# Preselector_-_Copy.net
KiCad netlist of a schematic drawn in EAGLE
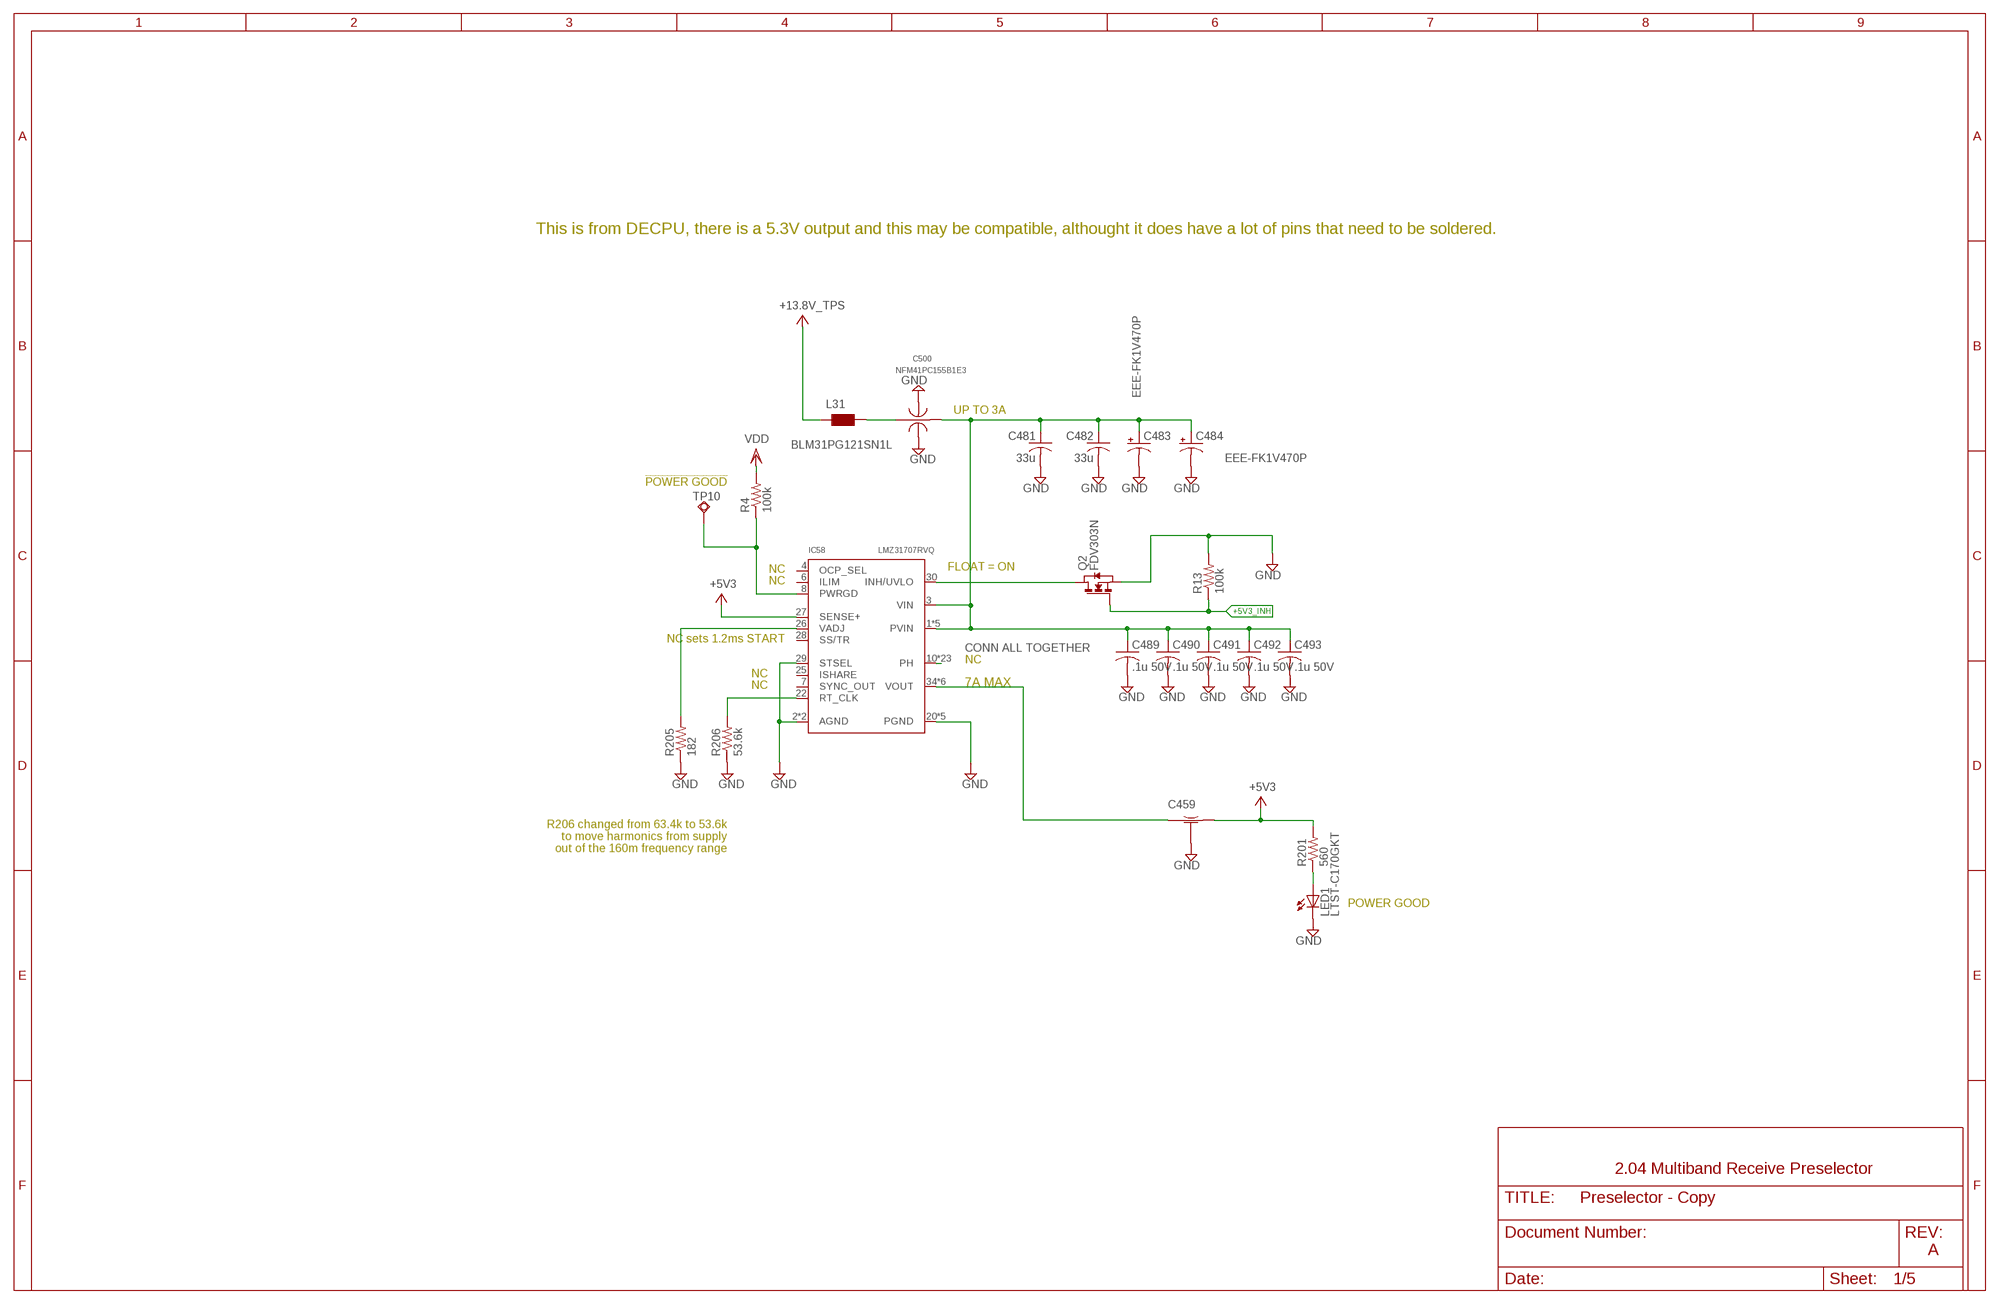
[diagram p0: schematic, sheet 1]
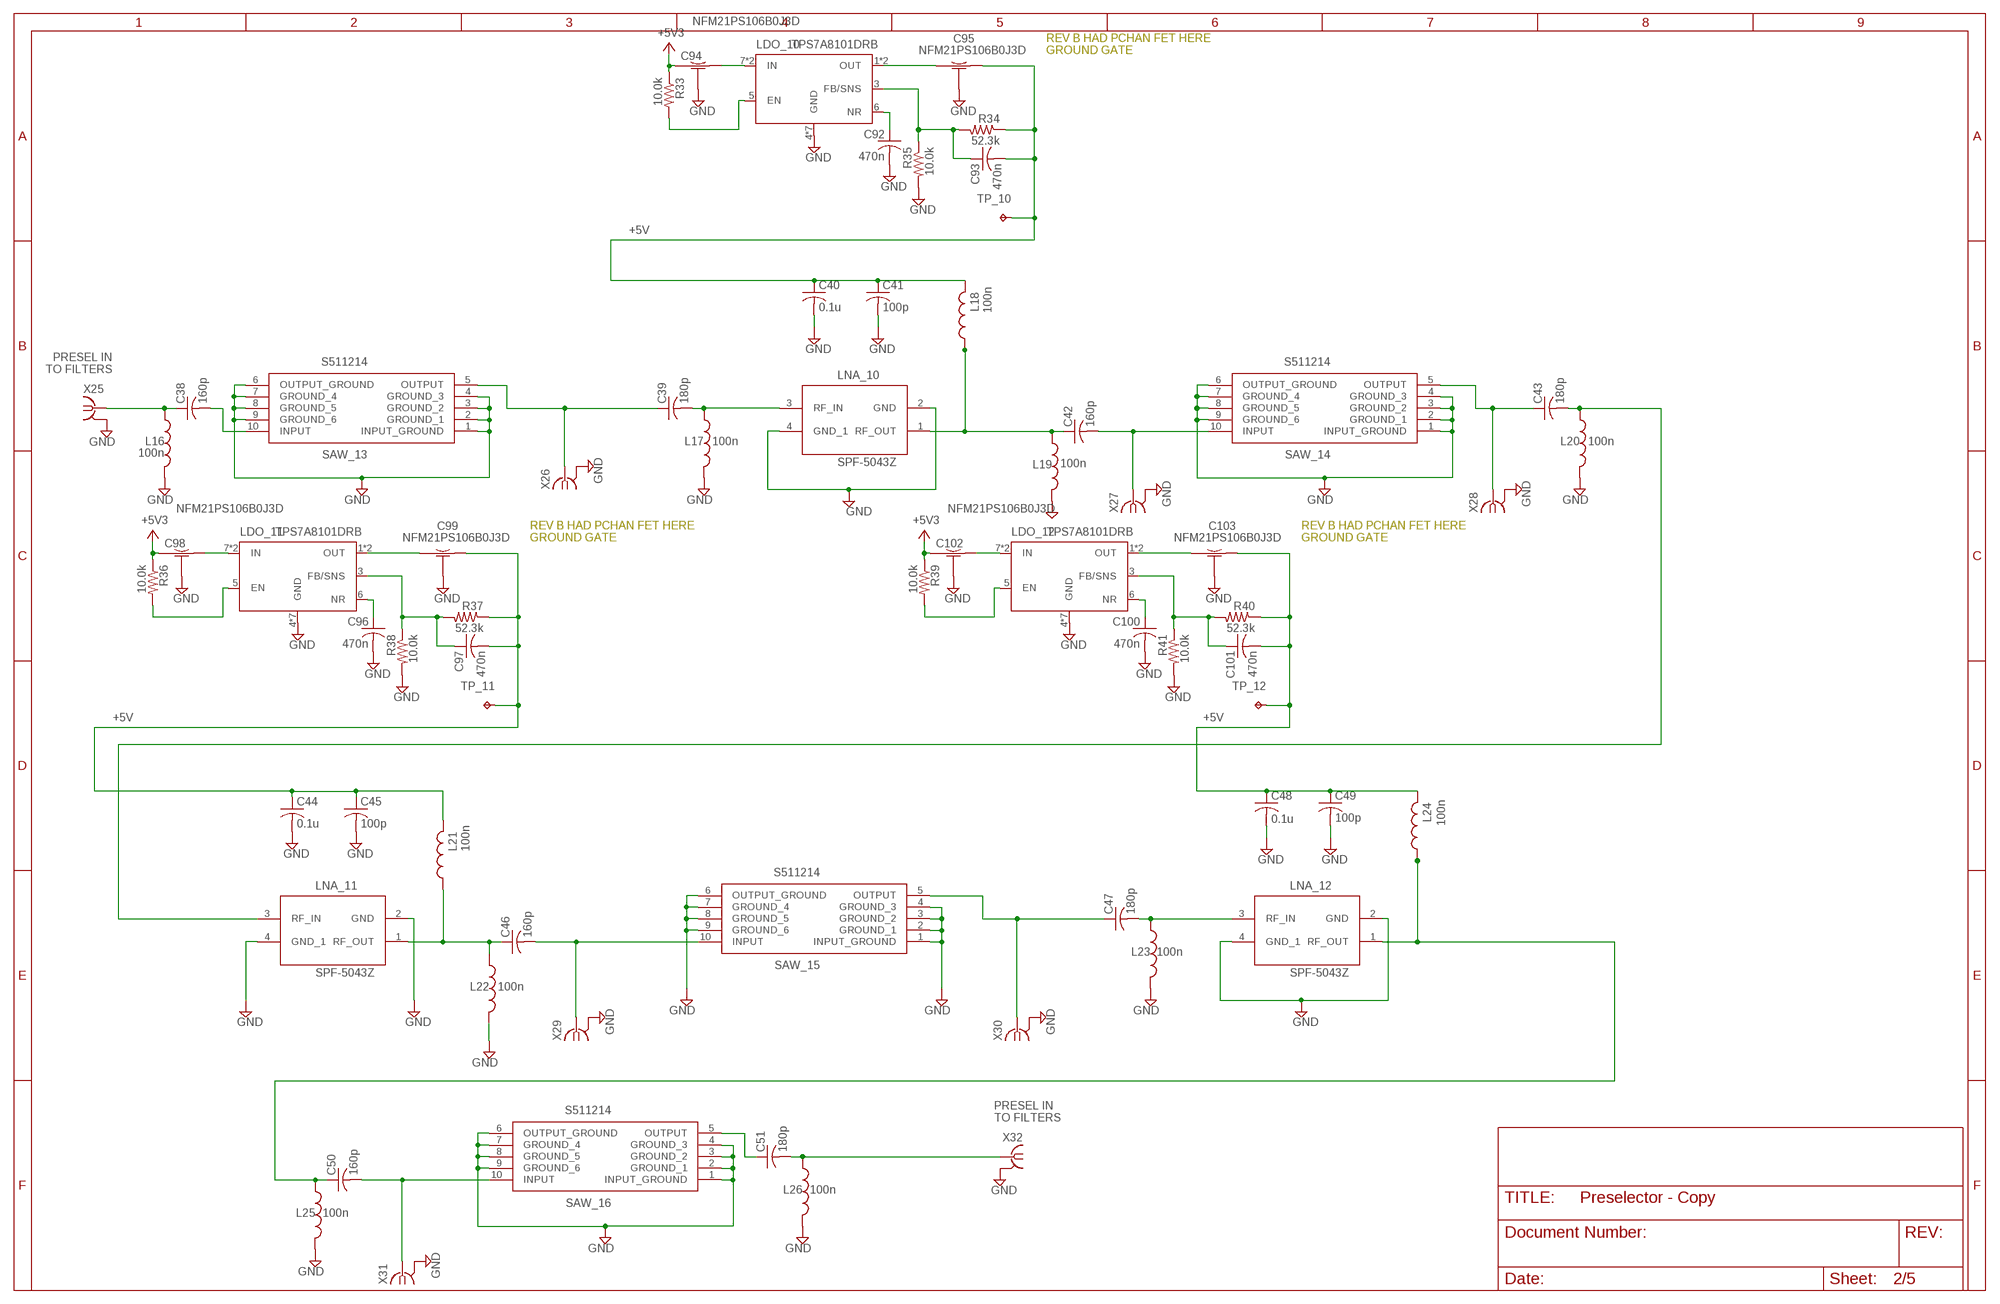
[diagram p1: schematic, sheet 2]
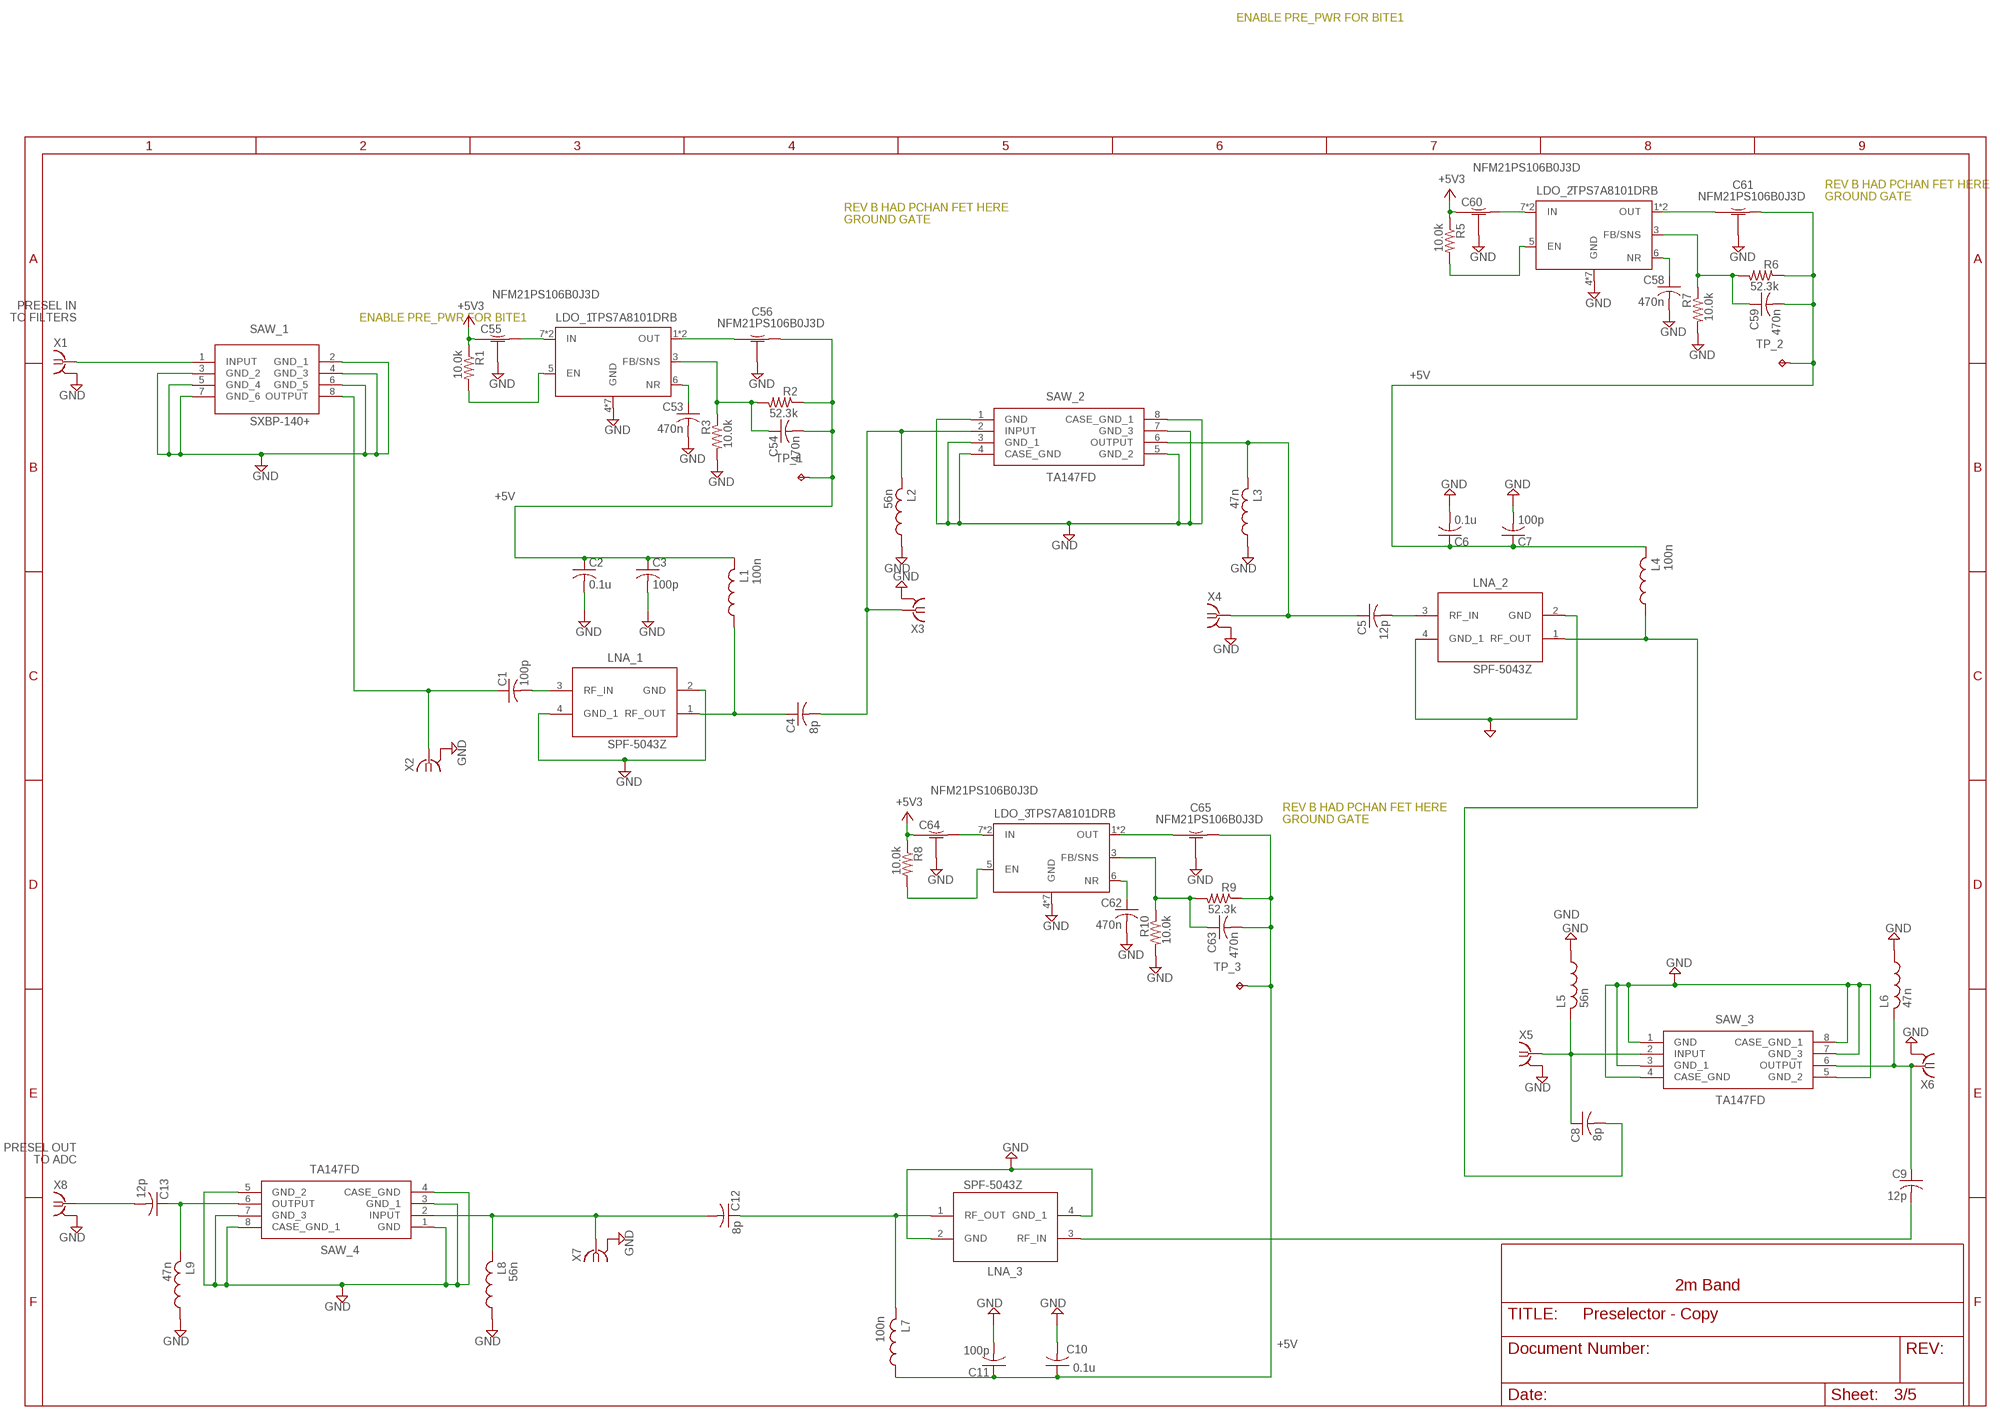
[diagram p2: schematic, sheet 3]
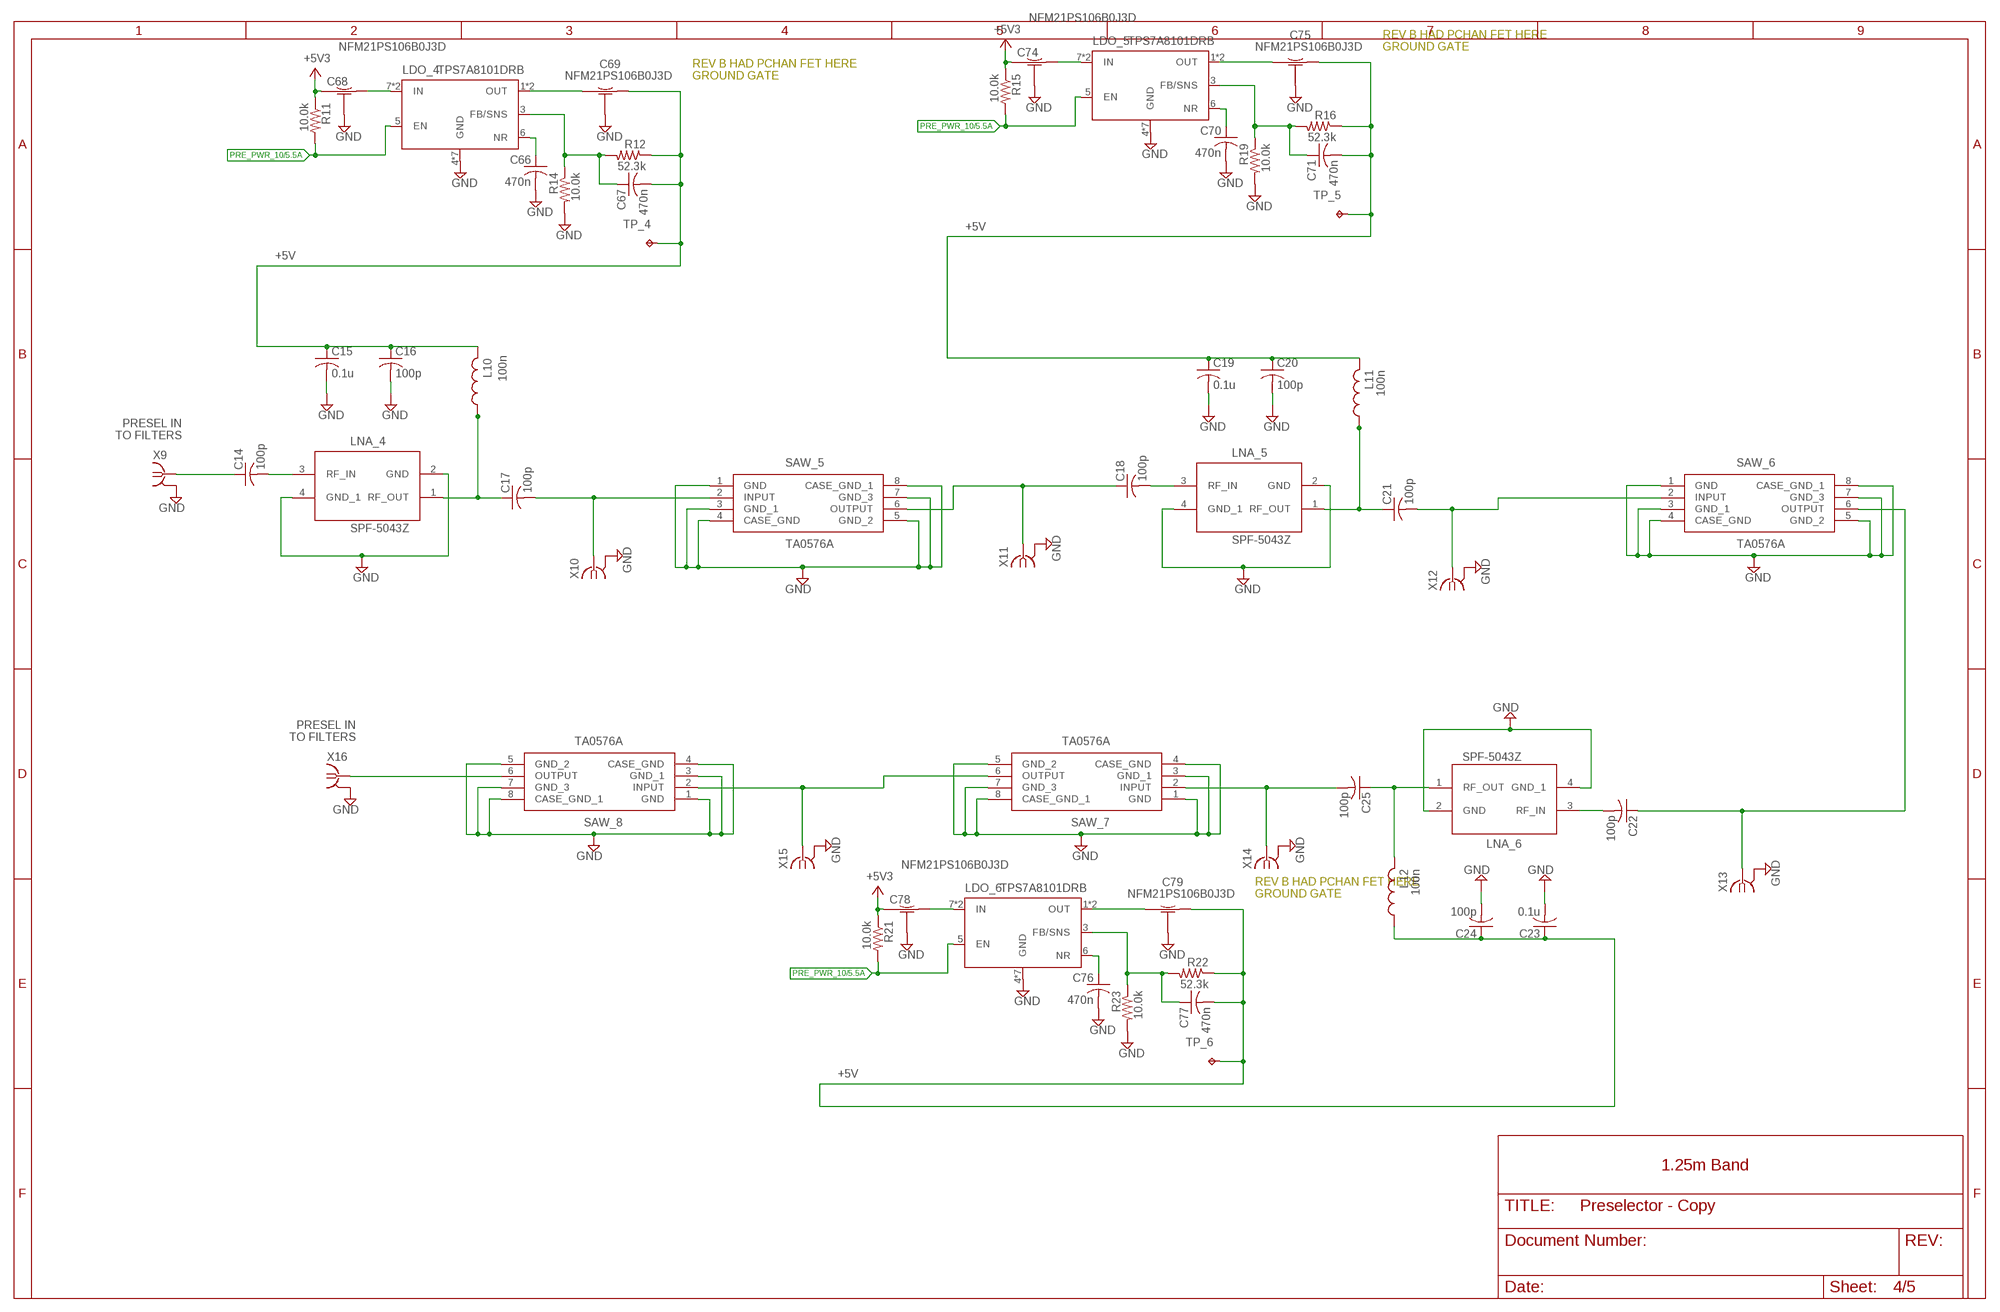
[diagram p3: schematic, sheet 4]
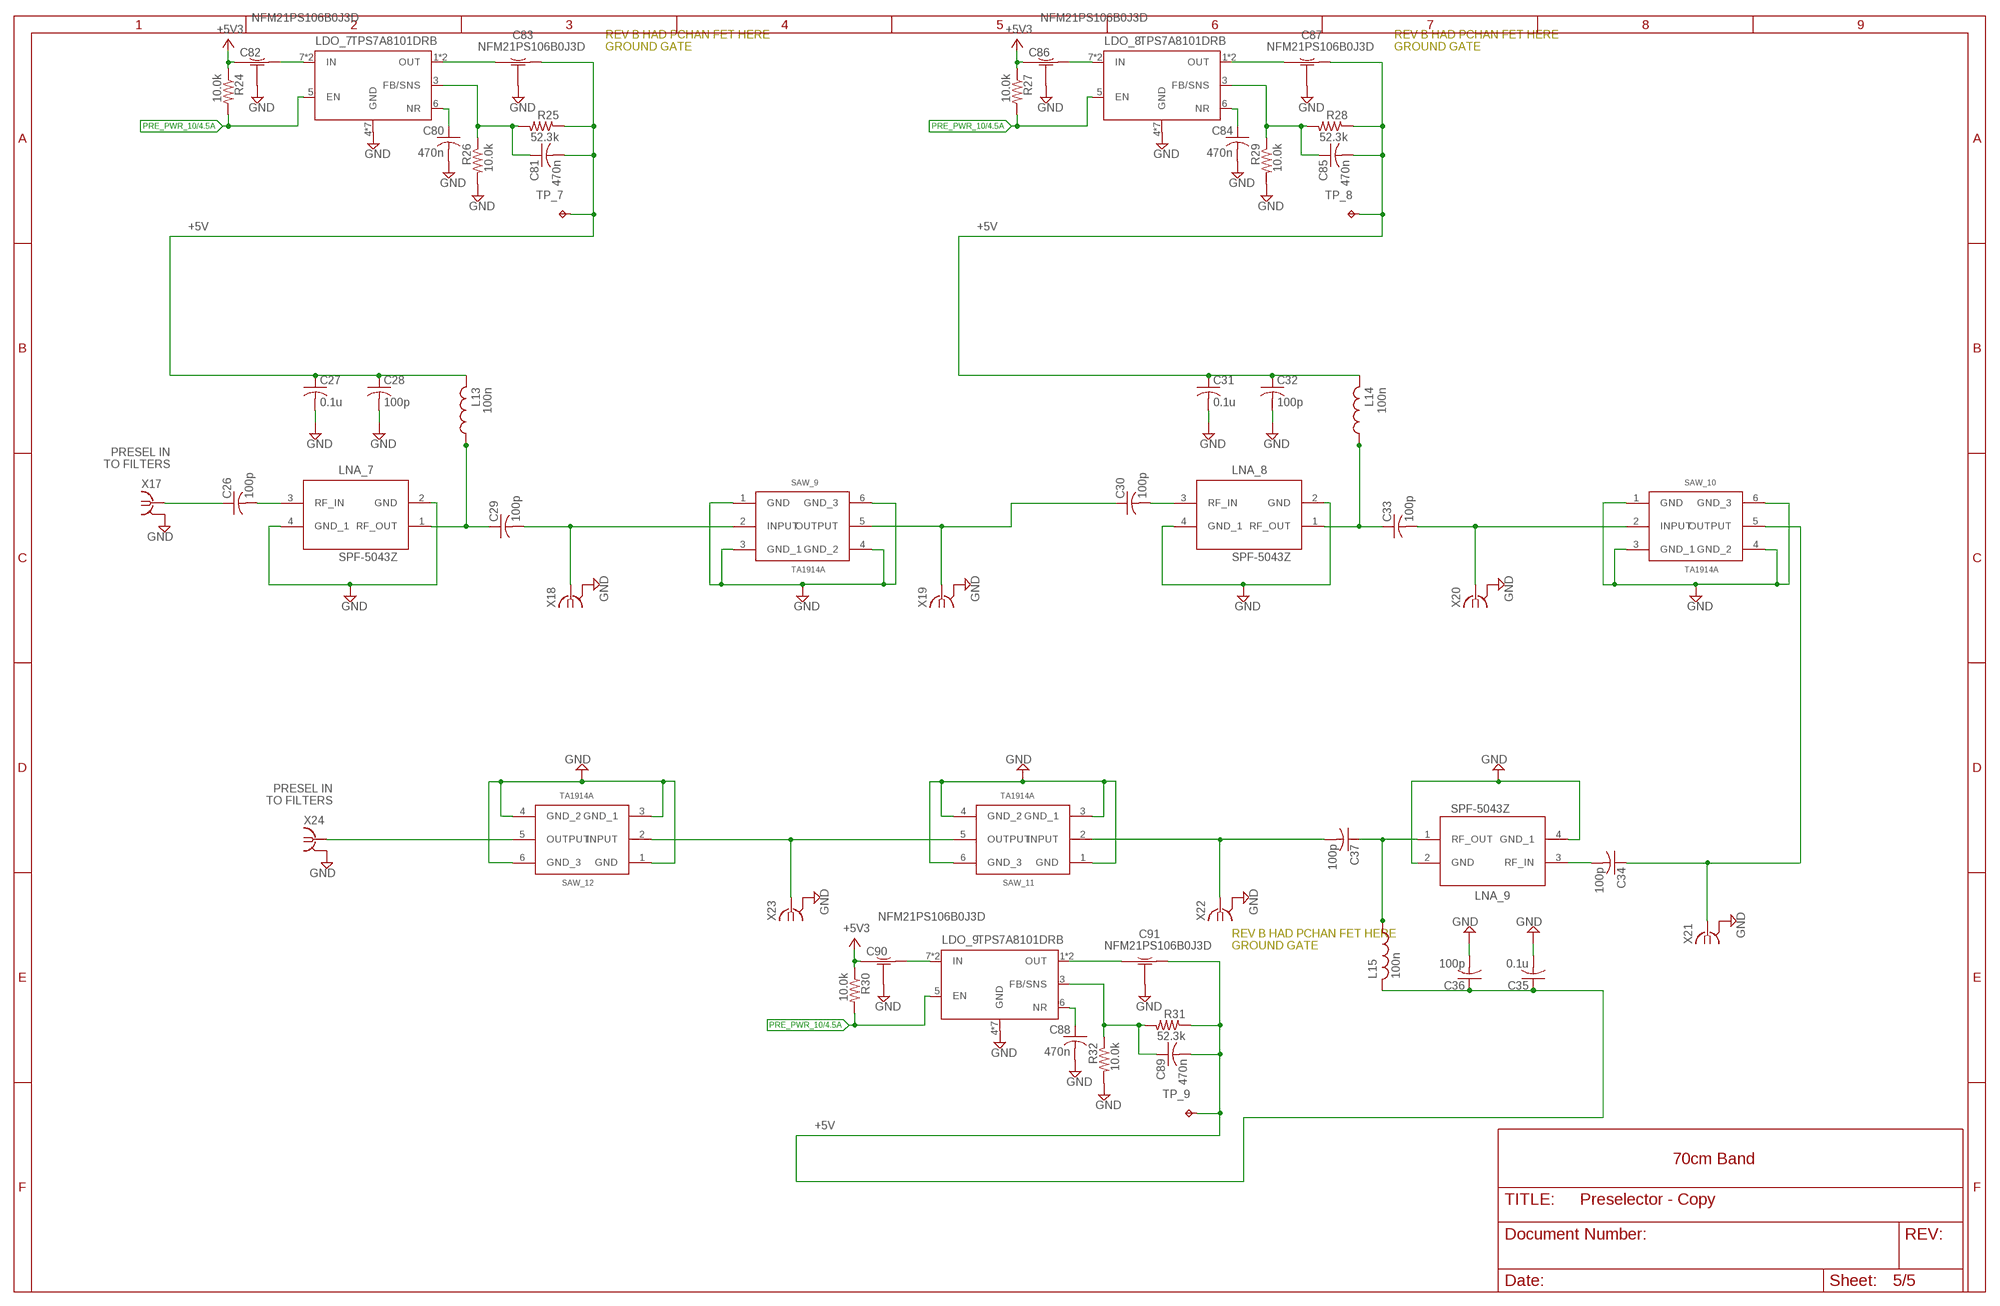
[diagram p4: schematic, sheet 5]

(export (version "E")
  (design (tool "Eeschema 10.0.6"))
  (components
    (comp (ref "C1")
      (value "100p")
      (footprint "eagle-import:C0603K")
      (libsource (lib "eagle-import") (part "C-USC0603K"))
    )
    (comp (ref "C2")
      (value "0.1u")
      (footprint "eagle-import:C0603K")
      (libsource (lib "eagle-import") (part "C-USC0603K"))
    )
    (comp (ref "C3")
      (value "100p")
      (footprint "eagle-import:C0603K")
      (libsource (lib "eagle-import") (part "C-USC0603K"))
    )
    (comp (ref "C4")
      (value "8p")
      (footprint "eagle-import:C0603K")
      (libsource (lib "eagle-import") (part "C-USC0603K"))
    )
    (comp (ref "C5")
      (value "12p")
      (footprint "eagle-import:C0603K")
      (libsource (lib "eagle-import") (part "C-USC0603K"))
    )
    (comp (ref "C6")
      (value "0.1u")
      (footprint "eagle-import:C0603K")
      (libsource (lib "eagle-import") (part "C-USC0603K"))
    )
    (comp (ref "C7")
      (value "100p")
      (footprint "eagle-import:C0603K")
      (libsource (lib "eagle-import") (part "C-USC0603K"))
    )
    (comp (ref "C8")
      (value "8p")
      (footprint "eagle-import:C0603K")
      (libsource (lib "eagle-import") (part "C-USC0603K"))
    )
    (comp (ref "C9")
      (value "12p")
      (footprint "eagle-import:C0603K")
      (libsource (lib "eagle-import") (part "C-USC0603K"))
    )
    (comp (ref "C10")
      (value "0.1u")
      (footprint "eagle-import:C0603K")
      (libsource (lib "eagle-import") (part "C-USC0603K"))
    )
    (comp (ref "C11")
      (value "100p")
      (footprint "eagle-import:C0603K")
      (libsource (lib "eagle-import") (part "C-USC0603K"))
    )
    (comp (ref "C12")
      (value "8p")
      (footprint "eagle-import:C0603K")
      (libsource (lib "eagle-import") (part "C-USC0603K"))
    )
    (comp (ref "C13")
      (value "12p")
      (footprint "eagle-import:C0603K")
      (libsource (lib "eagle-import") (part "C-USC0603K"))
    )
    (comp (ref "C53")
      (value "470n")
      (footprint "eagle-import:C0402K")
      (libsource (lib "eagle-import") (part "C-USC0402K"))
    )
    (comp (ref "C54")
      (value "470n")
      (footprint "eagle-import:C0402K")
      (libsource (lib "eagle-import") (part "C-USC0402K"))
    )
    (comp (ref "C55")
      (value "NFM21PS106B0J3D")
      (footprint "eagle-import:NFM21PS")
      (libsource (lib "eagle-import") (part "NFM21PS"))
    )
    (comp (ref "C56")
      (value "NFM21PS106B0J3D")
      (footprint "eagle-import:NFM21PS")
      (libsource (lib "eagle-import") (part "NFM21PS"))
    )
    (comp (ref "C58")
      (value "470n")
      (footprint "eagle-import:C0402K")
      (libsource (lib "eagle-import") (part "C-USC0402K"))
    )
    (comp (ref "C59")
      (value "470n")
      (footprint "eagle-import:C0402K")
      (libsource (lib "eagle-import") (part "C-USC0402K"))
    )
    (comp (ref "C60")
      (value "NFM21PS106B0J3D")
      (footprint "eagle-import:NFM21PS")
      (libsource (lib "eagle-import") (part "NFM21PS"))
    )
    (comp (ref "C61")
      (value "NFM21PS106B0J3D")
      (footprint "eagle-import:NFM21PS")
      (libsource (lib "eagle-import") (part "NFM21PS"))
    )
    (comp (ref "C62")
      (value "470n")
      (footprint "eagle-import:C0402K")
      (libsource (lib "eagle-import") (part "C-USC0402K"))
    )
    (comp (ref "C63")
      (value "470n")
      (footprint "eagle-import:C0402K")
      (libsource (lib "eagle-import") (part "C-USC0402K"))
    )
    (comp (ref "C64")
      (value "NFM21PS106B0J3D")
      (footprint "eagle-import:NFM21PS")
      (libsource (lib "eagle-import") (part "NFM21PS"))
    )
    (comp (ref "C65")
      (value "NFM21PS106B0J3D")
      (footprint "eagle-import:NFM21PS")
      (libsource (lib "eagle-import") (part "NFM21PS"))
    )
    (comp (ref "L1")
      (value "100n")
      (footprint "eagle-import:C1206")
      (libsource (lib "eagle-import") (part "L-US1206"))
    )
    (comp (ref "L2")
      (value "56n")
      (footprint "eagle-import:C1206")
      (libsource (lib "eagle-import") (part "L-US1206"))
    )
    (comp (ref "L3")
      (value "47n")
      (footprint "eagle-import:C1206")
      (libsource (lib "eagle-import") (part "L-US1206"))
    )
    (comp (ref "L4")
      (value "100n")
      (footprint "eagle-import:C1206")
      (libsource (lib "eagle-import") (part "L-US1206"))
    )
    (comp (ref "L5")
      (value "56n")
      (footprint "eagle-import:C1206")
      (libsource (lib "eagle-import") (part "L-US1206"))
    )
    (comp (ref "L6")
      (value "47n")
      (footprint "eagle-import:C1206")
      (libsource (lib "eagle-import") (part "L-US1206"))
    )
    (comp (ref "L7")
      (value "100n")
      (footprint "eagle-import:C1206")
      (libsource (lib "eagle-import") (part "L-US1206"))
    )
    (comp (ref "L8")
      (value "56n")
      (footprint "eagle-import:C1206")
      (libsource (lib "eagle-import") (part "L-US1206"))
    )
    (comp (ref "L9")
      (value "47n")
      (footprint "eagle-import:C1206")
      (libsource (lib "eagle-import") (part "L-US1206"))
    )
    (comp (ref "LDO_1")
      (value "TPS7A8101DRB")
      (footprint "eagle-import:DRB")
      (libsource (lib "eagle-import") (part "TPS7A8101DRB"))
    )
    (comp (ref "LDO_2")
      (value "TPS7A8101DRB")
      (footprint "eagle-import:DRB")
      (libsource (lib "eagle-import") (part "TPS7A8101DRB"))
    )
    (comp (ref "LDO_3")
      (value "TPS7A8101DRB")
      (footprint "eagle-import:DRB")
      (libsource (lib "eagle-import") (part "TPS7A8101DRB"))
    )
    (comp (ref "LNA_1")
      (value "SPF-5043Z")
      (footprint "eagle-import:SPF-5043Z")
      (libsource (lib "eagle-import") (part "SPF-5043Z"))
    )
    (comp (ref "LNA_2")
      (value "SPF-5043Z")
      (footprint "eagle-import:SPF-5043Z")
      (libsource (lib "eagle-import") (part "SPF-5043Z"))
    )
    (comp (ref "LNA_3")
      (value "SPF-5043Z")
      (footprint "eagle-import:SPF-5043Z")
      (libsource (lib "eagle-import") (part "SPF-5043Z"))
    )
    (comp (ref "R1")
      (value "10.0k")
      (footprint "eagle-import:R0603")
      (libsource (lib "eagle-import") (part "R-US_R0603"))
    )
    (comp (ref "R2")
      (value "52.3k")
      (footprint "eagle-import:R0603")
      (libsource (lib "eagle-import") (part "R-US_R0603"))
    )
    (comp (ref "R3")
      (value "10.0k")
      (footprint "eagle-import:R0603")
      (libsource (lib "eagle-import") (part "R-US_R0603"))
    )
    (comp (ref "R5")
      (value "10.0k")
      (footprint "eagle-import:R0603")
      (libsource (lib "eagle-import") (part "R-US_R0603"))
    )
    (comp (ref "R6")
      (value "52.3k")
      (footprint "eagle-import:R0603")
      (libsource (lib "eagle-import") (part "R-US_R0603"))
    )
    (comp (ref "R7")
      (value "10.0k")
      (footprint "eagle-import:R0603")
      (libsource (lib "eagle-import") (part "R-US_R0603"))
    )
    (comp (ref "R8")
      (value "10.0k")
      (footprint "eagle-import:R0603")
      (libsource (lib "eagle-import") (part "R-US_R0603"))
    )
    (comp (ref "R9")
      (value "52.3k")
      (footprint "eagle-import:R0603")
      (libsource (lib "eagle-import") (part "R-US_R0603"))
    )
    (comp (ref "R10")
      (value "10.0k")
      (footprint "eagle-import:R0603")
      (libsource (lib "eagle-import") (part "R-US_R0603"))
    )
    (comp (ref "SAW_1")
      (value "SXBP-140+")
      (footprint "eagle-import:SXBP-140+")
      (libsource (lib "eagle-import") (part "SXBP-140+"))
    )
    (comp (ref "SAW_2")
      (value "TA147FD")
      (footprint "eagle-import:TA147FD")
      (libsource (lib "eagle-import") (part "TA147FD"))
    )
    (comp (ref "SAW_3")
      (value "TA147FD")
      (footprint "eagle-import:TA147FD")
      (libsource (lib "eagle-import") (part "TA147FD"))
    )
    (comp (ref "SAW_4")
      (value "TA147FD")
      (footprint "eagle-import:TA147FD")
      (libsource (lib "eagle-import") (part "TA147FD"))
    )
    (comp (ref "TP_1")
      (value "TPTP20SQ")
      (footprint "eagle-import:TP20SQ")
      (libsource (lib "eagle-import") (part "TPTP20SQ"))
    )
    (comp (ref "TP_2")
      (value "TPTP20SQ")
      (footprint "eagle-import:TP20SQ")
      (libsource (lib "eagle-import") (part "TPTP20SQ"))
    )
    (comp (ref "TP_3")
      (value "TPTP20SQ")
      (footprint "eagle-import:TP20SQ")
      (libsource (lib "eagle-import") (part "TPTP20SQ"))
    )
    (comp (ref "X1")
      (value "0733660061")
      (footprint "eagle-import:BU-SMA-V")
      (libsource (lib "eagle-import") (part "BU-SMA-V"))
    )
    (comp (ref "X2")
      (value "0733660061")
      (footprint "eagle-import:BU-SMA-V")
      (libsource (lib "eagle-import") (part "BU-SMA-V"))
    )
    (comp (ref "X3")
      (value "0733660061")
      (footprint "eagle-import:BU-SMA-V")
      (libsource (lib "eagle-import") (part "BU-SMA-V"))
    )
    (comp (ref "X4")
      (value "0733660061")
      (footprint "eagle-import:BU-SMA-V")
      (libsource (lib "eagle-import") (part "BU-SMA-V"))
    )
    (comp (ref "X5")
      (value "0733660061")
      (footprint "eagle-import:BU-SMA-V")
      (libsource (lib "eagle-import") (part "BU-SMA-V"))
    )
    (comp (ref "X6")
      (value "0733660061")
      (footprint "eagle-import:BU-SMA-V")
      (libsource (lib "eagle-import") (part "BU-SMA-V"))
    )
    (comp (ref "X7")
      (value "0733660061")
      (footprint "eagle-import:BU-SMA-V")
      (libsource (lib "eagle-import") (part "BU-SMA-V"))
    )
    (comp (ref "X8")
      (value "0733660061")
      (footprint "eagle-import:BU-SMA-V")
      (libsource (lib "eagle-import") (part "BU-SMA-V"))
    )
    (comp (ref "C26")
      (value "100p")
      (footprint "eagle-import:C0603K")
      (libsource (lib "eagle-import") (part "C-USC0603K"))
    )
    (comp (ref "C27")
      (value "0.1u")
      (footprint "eagle-import:C0603K")
      (libsource (lib "eagle-import") (part "C-USC0603K"))
    )
    (comp (ref "C28")
      (value "100p")
      (footprint "eagle-import:C0603K")
      (libsource (lib "eagle-import") (part "C-USC0603K"))
    )
    (comp (ref "C29")
      (value "100p")
      (footprint "eagle-import:C0603K")
      (libsource (lib "eagle-import") (part "C-USC0603K"))
    )
    (comp (ref "C30")
      (value "100p")
      (footprint "eagle-import:C0603K")
      (libsource (lib "eagle-import") (part "C-USC0603K"))
    )
    (comp (ref "C31")
      (value "0.1u")
      (footprint "eagle-import:C0603K")
      (libsource (lib "eagle-import") (part "C-USC0603K"))
    )
    (comp (ref "C32")
      (value "100p")
      (footprint "eagle-import:C0603K")
      (libsource (lib "eagle-import") (part "C-USC0603K"))
    )
    (comp (ref "C33")
      (value "100p")
      (footprint "eagle-import:C0603K")
      (libsource (lib "eagle-import") (part "C-USC0603K"))
    )
    (comp (ref "C34")
      (value "100p")
      (footprint "eagle-import:C0603K")
      (libsource (lib "eagle-import") (part "C-USC0603K"))
    )
    (comp (ref "C35")
      (value "0.1u")
      (footprint "eagle-import:C0603K")
      (libsource (lib "eagle-import") (part "C-USC0603K"))
    )
    (comp (ref "C36")
      (value "100p")
      (footprint "eagle-import:C0603K")
      (libsource (lib "eagle-import") (part "C-USC0603K"))
    )
    (comp (ref "C37")
      (value "100p")
      (footprint "eagle-import:C0603K")
      (libsource (lib "eagle-import") (part "C-USC0603K"))
    )
    (comp (ref "C80")
      (value "470n")
      (footprint "eagle-import:C0402K")
      (libsource (lib "eagle-import") (part "C-USC0402K"))
    )
    (comp (ref "C81")
      (value "470n")
      (footprint "eagle-import:C0402K")
      (libsource (lib "eagle-import") (part "C-USC0402K"))
    )
    (comp (ref "C82")
      (value "NFM21PS106B0J3D")
      (footprint "eagle-import:NFM21PS")
      (libsource (lib "eagle-import") (part "NFM21PS"))
    )
    (comp (ref "C83")
      (value "NFM21PS106B0J3D")
      (footprint "eagle-import:NFM21PS")
      (libsource (lib "eagle-import") (part "NFM21PS"))
    )
    (comp (ref "C84")
      (value "470n")
      (footprint "eagle-import:C0402K")
      (libsource (lib "eagle-import") (part "C-USC0402K"))
    )
    (comp (ref "C85")
      (value "470n")
      (footprint "eagle-import:C0402K")
      (libsource (lib "eagle-import") (part "C-USC0402K"))
    )
    (comp (ref "C86")
      (value "NFM21PS106B0J3D")
      (footprint "eagle-import:NFM21PS")
      (libsource (lib "eagle-import") (part "NFM21PS"))
    )
    (comp (ref "C87")
      (value "NFM21PS106B0J3D")
      (footprint "eagle-import:NFM21PS")
      (libsource (lib "eagle-import") (part "NFM21PS"))
    )
    (comp (ref "C88")
      (value "470n")
      (footprint "eagle-import:C0402K")
      (libsource (lib "eagle-import") (part "C-USC0402K"))
    )
    (comp (ref "C89")
      (value "470n")
      (footprint "eagle-import:C0402K")
      (libsource (lib "eagle-import") (part "C-USC0402K"))
    )
    (comp (ref "C90")
      (value "NFM21PS106B0J3D")
      (footprint "eagle-import:NFM21PS")
      (libsource (lib "eagle-import") (part "NFM21PS"))
    )
    (comp (ref "C91")
      (value "NFM21PS106B0J3D")
      (footprint "eagle-import:NFM21PS")
      (libsource (lib "eagle-import") (part "NFM21PS"))
    )
    (comp (ref "L13")
      (value "100n")
      (footprint "eagle-import:C1206")
      (libsource (lib "eagle-import") (part "L-US1206"))
    )
    (comp (ref "L14")
      (value "100n")
      (footprint "eagle-import:C1206")
      (libsource (lib "eagle-import") (part "L-US1206"))
    )
    (comp (ref "L15")
      (value "100n")
      (footprint "eagle-import:C1206")
      (libsource (lib "eagle-import") (part "L-US1206"))
    )
    (comp (ref "LDO_7")
      (value "TPS7A8101DRB")
      (footprint "eagle-import:DRB")
      (libsource (lib "eagle-import") (part "TPS7A8101DRB"))
    )
    (comp (ref "LDO_8")
      (value "TPS7A8101DRB")
      (footprint "eagle-import:DRB")
      (libsource (lib "eagle-import") (part "TPS7A8101DRB"))
    )
    (comp (ref "LDO_9")
      (value "TPS7A8101DRB")
      (footprint "eagle-import:DRB")
      (libsource (lib "eagle-import") (part "TPS7A8101DRB"))
    )
    (comp (ref "LNA_7")
      (value "SPF-5043Z")
      (footprint "eagle-import:SPF-5043Z")
      (libsource (lib "eagle-import") (part "SPF-5043Z"))
    )
    (comp (ref "LNA_8")
      (value "SPF-5043Z")
      (footprint "eagle-import:SPF-5043Z")
      (libsource (lib "eagle-import") (part "SPF-5043Z"))
    )
    (comp (ref "LNA_9")
      (value "SPF-5043Z")
      (footprint "eagle-import:SPF-5043Z")
      (libsource (lib "eagle-import") (part "SPF-5043Z"))
    )
    (comp (ref "R24")
      (value "10.0k")
      (footprint "eagle-import:R0603")
      (libsource (lib "eagle-import") (part "R-US_R0603"))
    )
    (comp (ref "R25")
      (value "52.3k")
      (footprint "eagle-import:R0603")
      (libsource (lib "eagle-import") (part "R-US_R0603"))
    )
    (comp (ref "R26")
      (value "10.0k")
      (footprint "eagle-import:R0603")
      (libsource (lib "eagle-import") (part "R-US_R0603"))
    )
    (comp (ref "R27")
      (value "10.0k")
      (footprint "eagle-import:R0603")
      (libsource (lib "eagle-import") (part "R-US_R0603"))
    )
    (comp (ref "R28")
      (value "52.3k")
      (footprint "eagle-import:R0603")
      (libsource (lib "eagle-import") (part "R-US_R0603"))
    )
    (comp (ref "R29")
      (value "10.0k")
      (footprint "eagle-import:R0603")
      (libsource (lib "eagle-import") (part "R-US_R0603"))
    )
    (comp (ref "R30")
      (value "10.0k")
      (footprint "eagle-import:R0603")
      (libsource (lib "eagle-import") (part "R-US_R0603"))
    )
    (comp (ref "R31")
      (value "52.3k")
      (footprint "eagle-import:R0603")
      (libsource (lib "eagle-import") (part "R-US_R0603"))
    )
    (comp (ref "R32")
      (value "10.0k")
      (footprint "eagle-import:R0603")
      (libsource (lib "eagle-import") (part "R-US_R0603"))
    )
    (comp (ref "SAW_9")
      (value "TA1914A")
      (footprint "eagle-import:TA1914A")
      (libsource (lib "eagle-import") (part "TA1914A"))
    )
    (comp (ref "SAW_10")
      (value "TA1914A")
      (footprint "eagle-import:TA1914A")
      (libsource (lib "eagle-import") (part "TA1914A"))
    )
    (comp (ref "SAW_11")
      (value "TA1914A")
      (footprint "eagle-import:TA1914A")
      (libsource (lib "eagle-import") (part "TA1914A"))
    )
    (comp (ref "SAW_12")
      (value "TA1914A")
      (footprint "eagle-import:TA1914A")
      (libsource (lib "eagle-import") (part "TA1914A"))
    )
    (comp (ref "TP_7")
      (value "TPTP20SQ")
      (footprint "eagle-import:TP20SQ")
      (libsource (lib "eagle-import") (part "TPTP20SQ"))
    )
    (comp (ref "TP_8")
      (value "TPTP20SQ")
      (footprint "eagle-import:TP20SQ")
      (libsource (lib "eagle-import") (part "TPTP20SQ"))
    )
    (comp (ref "TP_9")
      (value "TPTP20SQ")
      (footprint "eagle-import:TP20SQ")
      (libsource (lib "eagle-import") (part "TPTP20SQ"))
    )
    (comp (ref "X17")
      (value "0733660061")
      (footprint "eagle-import:BU-SMA-V")
      (libsource (lib "eagle-import") (part "BU-SMA-V"))
    )
    (comp (ref "X18")
      (value "0733660061")
      (footprint "eagle-import:BU-SMA-V")
      (libsource (lib "eagle-import") (part "BU-SMA-V"))
    )
    (comp (ref "X19")
      (value "0733660061")
      (footprint "eagle-import:BU-SMA-V")
      (libsource (lib "eagle-import") (part "BU-SMA-V"))
    )
    (comp (ref "X20")
      (value "0733660061")
      (footprint "eagle-import:BU-SMA-V")
      (libsource (lib "eagle-import") (part "BU-SMA-V"))
    )
    (comp (ref "X21")
      (value "0733660061")
      (footprint "eagle-import:BU-SMA-V")
      (libsource (lib "eagle-import") (part "BU-SMA-V"))
    )
    (comp (ref "X22")
      (value "0733660061")
      (footprint "eagle-import:BU-SMA-V")
      (libsource (lib "eagle-import") (part "BU-SMA-V"))
    )
    (comp (ref "X23")
      (value "0733660061")
      (footprint "eagle-import:BU-SMA-V")
      (libsource (lib "eagle-import") (part "BU-SMA-V"))
    )
    (comp (ref "X24")
      (value "0733660061")
      (footprint "eagle-import:BU-SMA-V")
      (libsource (lib "eagle-import") (part "BU-SMA-V"))
    )
    (comp (ref "C14")
      (value "100p")
      (footprint "eagle-import:C0603K")
      (libsource (lib "eagle-import") (part "C-USC0603K"))
    )
    (comp (ref "C15")
      (value "0.1u")
      (footprint "eagle-import:C0603K")
      (libsource (lib "eagle-import") (part "C-USC0603K"))
    )
    (comp (ref "C16")
      (value "100p")
      (footprint "eagle-import:C0603K")
      (libsource (lib "eagle-import") (part "C-USC0603K"))
    )
    (comp (ref "C17")
      (value "100p")
      (footprint "eagle-import:C0603K")
      (libsource (lib "eagle-import") (part "C-USC0603K"))
    )
    (comp (ref "C18")
      (value "100p")
      (footprint "eagle-import:C0603K")
      (libsource (lib "eagle-import") (part "C-USC0603K"))
    )
    (comp (ref "C19")
      (value "0.1u")
      (footprint "eagle-import:C0603K")
      (libsource (lib "eagle-import") (part "C-USC0603K"))
    )
    (comp (ref "C20")
      (value "100p")
      (footprint "eagle-import:C0603K")
      (libsource (lib "eagle-import") (part "C-USC0603K"))
    )
    (comp (ref "C21")
      (value "100p")
      (footprint "eagle-import:C0603K")
      (libsource (lib "eagle-import") (part "C-USC0603K"))
    )
    (comp (ref "C22")
      (value "100p")
      (footprint "eagle-import:C0603K")
      (libsource (lib "eagle-import") (part "C-USC0603K"))
    )
    (comp (ref "C23")
      (value "0.1u")
      (footprint "eagle-import:C0603K")
      (libsource (lib "eagle-import") (part "C-USC0603K"))
    )
    (comp (ref "C24")
      (value "100p")
      (footprint "eagle-import:C0603K")
      (libsource (lib "eagle-import") (part "C-USC0603K"))
    )
    (comp (ref "C25")
      (value "100p")
      (footprint "eagle-import:C0603K")
      (libsource (lib "eagle-import") (part "C-USC0603K"))
    )
    (comp (ref "C66")
      (value "470n")
      (footprint "eagle-import:C0402K")
      (libsource (lib "eagle-import") (part "C-USC0402K"))
    )
    (comp (ref "C67")
      (value "470n")
      (footprint "eagle-import:C0402K")
      (libsource (lib "eagle-import") (part "C-USC0402K"))
    )
    (comp (ref "C68")
      (value "NFM21PS106B0J3D")
      (footprint "eagle-import:NFM21PS")
      (libsource (lib "eagle-import") (part "NFM21PS"))
    )
    (comp (ref "C69")
      (value "NFM21PS106B0J3D")
      (footprint "eagle-import:NFM21PS")
      (libsource (lib "eagle-import") (part "NFM21PS"))
    )
    (comp (ref "C70")
      (value "470n")
      (footprint "eagle-import:C0402K")
      (libsource (lib "eagle-import") (part "C-USC0402K"))
    )
    (comp (ref "C71")
      (value "470n")
      (footprint "eagle-import:C0402K")
      (libsource (lib "eagle-import") (part "C-USC0402K"))
    )
    (comp (ref "C74")
      (value "NFM21PS106B0J3D")
      (footprint "eagle-import:NFM21PS")
      (libsource (lib "eagle-import") (part "NFM21PS"))
    )
    (comp (ref "C75")
      (value "NFM21PS106B0J3D")
      (footprint "eagle-import:NFM21PS")
      (libsource (lib "eagle-import") (part "NFM21PS"))
    )
    (comp (ref "C76")
      (value "470n")
      (footprint "eagle-import:C0402K")
      (libsource (lib "eagle-import") (part "C-USC0402K"))
    )
    (comp (ref "C77")
      (value "470n")
      (footprint "eagle-import:C0402K")
      (libsource (lib "eagle-import") (part "C-USC0402K"))
    )
    (comp (ref "C78")
      (value "NFM21PS106B0J3D")
      (footprint "eagle-import:NFM21PS")
      (libsource (lib "eagle-import") (part "NFM21PS"))
    )
    (comp (ref "C79")
      (value "NFM21PS106B0J3D")
      (footprint "eagle-import:NFM21PS")
      (libsource (lib "eagle-import") (part "NFM21PS"))
    )
    (comp (ref "L10")
      (value "100n")
      (footprint "eagle-import:C1206")
      (libsource (lib "eagle-import") (part "L-US1206"))
    )
    (comp (ref "L11")
      (value "100n")
      (footprint "eagle-import:C1206")
      (libsource (lib "eagle-import") (part "L-US1206"))
    )
    (comp (ref "L12")
      (value "100n")
      (footprint "eagle-import:C1206")
      (libsource (lib "eagle-import") (part "L-US1206"))
    )
    (comp (ref "LDO_4")
      (value "TPS7A8101DRB")
      (footprint "eagle-import:DRB")
      (libsource (lib "eagle-import") (part "TPS7A8101DRB"))
    )
    (comp (ref "LDO_5")
      (value "TPS7A8101DRB")
      (footprint "eagle-import:DRB")
      (libsource (lib "eagle-import") (part "TPS7A8101DRB"))
    )
    (comp (ref "LDO_6")
      (value "TPS7A8101DRB")
      (footprint "eagle-import:DRB")
      (libsource (lib "eagle-import") (part "TPS7A8101DRB"))
    )
    (comp (ref "LNA_4")
      (value "SPF-5043Z")
      (footprint "eagle-import:SPF-5043Z")
      (libsource (lib "eagle-import") (part "SPF-5043Z"))
    )
    (comp (ref "LNA_5")
      (value "SPF-5043Z")
      (footprint "eagle-import:SPF-5043Z")
      (libsource (lib "eagle-import") (part "SPF-5043Z"))
    )
    (comp (ref "LNA_6")
      (value "SPF-5043Z")
      (footprint "eagle-import:SPF-5043Z")
      (libsource (lib "eagle-import") (part "SPF-5043Z"))
    )
    (comp (ref "R11")
      (value "10.0k")
      (footprint "eagle-import:R0603")
      (libsource (lib "eagle-import") (part "R-US_R0603"))
    )
    (comp (ref "R12")
      (value "52.3k")
      (footprint "eagle-import:R0603")
      (libsource (lib "eagle-import") (part "R-US_R0603"))
    )
    (comp (ref "R14")
      (value "10.0k")
      (footprint "eagle-import:R0603")
      (libsource (lib "eagle-import") (part "R-US_R0603"))
    )
    (comp (ref "R15")
      (value "10.0k")
      (footprint "eagle-import:R0603")
      (libsource (lib "eagle-import") (part "R-US_R0603"))
    )
    (comp (ref "R16")
      (value "52.3k")
      (footprint "eagle-import:R0603")
      (libsource (lib "eagle-import") (part "R-US_R0603"))
    )
    (comp (ref "R19")
      (value "10.0k")
      (footprint "eagle-import:R0603")
      (libsource (lib "eagle-import") (part "R-US_R0603"))
    )
    (comp (ref "R21")
      (value "10.0k")
      (footprint "eagle-import:R0603")
      (libsource (lib "eagle-import") (part "R-US_R0603"))
    )
    (comp (ref "R22")
      (value "52.3k")
      (footprint "eagle-import:R0603")
      (libsource (lib "eagle-import") (part "R-US_R0603"))
    )
    (comp (ref "R23")
      (value "10.0k")
      (footprint "eagle-import:R0603")
      (libsource (lib "eagle-import") (part "R-US_R0603"))
    )
    (comp (ref "SAW_5")
      (value "TA0576A")
      (footprint "eagle-import:TA0576A")
      (libsource (lib "eagle-import") (part "TA0576A"))
    )
    (comp (ref "SAW_6")
      (value "TA0576A")
      (footprint "eagle-import:TA0576A")
      (libsource (lib "eagle-import") (part "TA0576A"))
    )
    (comp (ref "SAW_7")
      (value "TA0576A")
      (footprint "eagle-import:TA0576A")
      (libsource (lib "eagle-import") (part "TA0576A"))
    )
    (comp (ref "SAW_8")
      (value "TA0576A")
      (footprint "eagle-import:TA0576A")
      (libsource (lib "eagle-import") (part "TA0576A"))
    )
    (comp (ref "TP_4")
      (value "TPTP20SQ")
      (footprint "eagle-import:TP20SQ")
      (libsource (lib "eagle-import") (part "TPTP20SQ"))
    )
    (comp (ref "TP_5")
      (value "TPTP20SQ")
      (footprint "eagle-import:TP20SQ")
      (libsource (lib "eagle-import") (part "TPTP20SQ"))
    )
    (comp (ref "TP_6")
      (value "TPTP20SQ")
      (footprint "eagle-import:TP20SQ")
      (libsource (lib "eagle-import") (part "TPTP20SQ"))
    )
    (comp (ref "X9")
      (value "0733660061")
      (footprint "eagle-import:BU-SMA-V")
      (libsource (lib "eagle-import") (part "BU-SMA-V"))
    )
    (comp (ref "X10")
      (value "0733660061")
      (footprint "eagle-import:BU-SMA-V")
      (libsource (lib "eagle-import") (part "BU-SMA-V"))
    )
    (comp (ref "X11")
      (value "0733660061")
      (footprint "eagle-import:BU-SMA-V")
      (libsource (lib "eagle-import") (part "BU-SMA-V"))
    )
    (comp (ref "X12")
      (value "0733660061")
      (footprint "eagle-import:BU-SMA-V")
      (libsource (lib "eagle-import") (part "BU-SMA-V"))
    )
    (comp (ref "X13")
      (value "0733660061")
      (footprint "eagle-import:BU-SMA-V")
      (libsource (lib "eagle-import") (part "BU-SMA-V"))
    )
    (comp (ref "X14")
      (value "0733660061")
      (footprint "eagle-import:BU-SMA-V")
      (libsource (lib "eagle-import") (part "BU-SMA-V"))
    )
    (comp (ref "X15")
      (value "0733660061")
      (footprint "eagle-import:BU-SMA-V")
      (libsource (lib "eagle-import") (part "BU-SMA-V"))
    )
    (comp (ref "X16")
      (value "0733660061")
      (footprint "eagle-import:BU-SMA-V")
      (libsource (lib "eagle-import") (part "BU-SMA-V"))
    )
    (comp (ref "C459")
      (value "NFM31PC276B0J3L")
      (footprint "eagle-import:NFM31PC276")
      (libsource (lib "eagle-import") (part "NFM31PC276B0J3L"))
    )
    (comp (ref "C481")
      (value "33u")
      (footprint "eagle-import:C1206K")
      (libsource (lib "eagle-import") (part "C-USC1206K"))
    )
    (comp (ref "C482")
      (value "33u")
      (footprint "eagle-import:C1206K")
      (libsource (lib "eagle-import") (part "C-USC1206K"))
    )
    (comp (ref "C483")
      (value "EEE-FK1V470P")
      (footprint "eagle-import:PANASONIC_D")
      (fields (field (name "PN") "EEE-FK1V470P"))
      (libsource (lib "eagle-import") (part "CPOL-USD"))
    )
    (comp (ref "C484")
      (value "EEE-FK1V470P")
      (footprint "eagle-import:PANASONIC_D")
      (fields (field (name "PN") "EEE-FK1V470P"))
      (libsource (lib "eagle-import") (part "CPOL-USD"))
    )
    (comp (ref "C489")
      (value ".1u 50V")
      (footprint "eagle-import:C0402K")
      (libsource (lib "eagle-import") (part "C-USC0402K"))
    )
    (comp (ref "C490")
      (value ".1u 50V")
      (footprint "eagle-import:C0402K")
      (libsource (lib "eagle-import") (part "C-USC0402K"))
    )
    (comp (ref "C491")
      (value ".1u 50V")
      (footprint "eagle-import:C0402K")
      (libsource (lib "eagle-import") (part "C-USC0402K"))
    )
    (comp (ref "C492")
      (value ".1u 50V")
      (footprint "eagle-import:C0402K")
      (libsource (lib "eagle-import") (part "C-USC0402K"))
    )
    (comp (ref "C493")
      (value ".1u 50V")
      (footprint "eagle-import:C0402K")
      (libsource (lib "eagle-import") (part "C-USC0402K"))
    )
    (comp (ref "C500")
      (value "NFM41PC155B1E3")
      (footprint "eagle-import:NFM1806")
      (libsource (lib "eagle-import") (part "NFM41PC155B1E3"))
    )
    (comp (ref "IC58")
      (value "LMZ31707RVQ")
      (footprint "eagle-import:RVQ")
      (libsource (lib "eagle-import") (part "LMZ31707RVQ"))
    )
    (comp (ref "L31")
      (value "BLM31PG121SN1L")
      (footprint "eagle-import:1206")
      (libsource (lib "eagle-import") (part "WE-CBF_1206"))
    )
    (comp (ref "LED1")
      (value "LTST-C170GKT")
      (footprint "eagle-import:CHIPLED_0805")
      (libsource (lib "eagle-import") (part "LEDCHIPLED_0805"))
    )
    (comp (ref "Q2")
      (value "FDV303N")
      (footprint "eagle-import:SOT-23")
      (libsource (lib "eagle-import") (part "NMOSSOT23"))
    )
    (comp (ref "R4")
      (value "100k")
      (footprint "eagle-import:R0201")
      (libsource (lib "eagle-import") (part "R-US_R0201"))
    )
    (comp (ref "R13")
      (value "100k")
      (footprint "eagle-import:R0201")
      (libsource (lib "eagle-import") (part "R-US_R0201"))
    )
    (comp (ref "R201")
      (value "560")
      (footprint "eagle-import:R0603")
      (libsource (lib "eagle-import") (part "R-US_R0603"))
    )
    (comp (ref "R205")
      (value "182")
      (footprint "eagle-import:R0603")
      (libsource (lib "eagle-import") (part "R-US_R0603"))
    )
    (comp (ref "R206")
      (value "53.6k")
      (footprint "eagle-import:R0603")
      (libsource (lib "eagle-import") (part "R-US_R0603"))
    )
    (comp (ref "TP10")
      (value "TPSQB1,27")
      (footprint "eagle-import:B1,27")
      (libsource (lib "eagle-import") (part "TPSQB1,27"))
    )
    (comp (ref "C38")
      (value "160p")
      (footprint "eagle-import:C0603K")
      (libsource (lib "eagle-import") (part "C-USC0603K"))
    )
    (comp (ref "C39")
      (value "180p")
      (footprint "eagle-import:C0603K")
      (libsource (lib "eagle-import") (part "C-USC0603K"))
    )
    (comp (ref "C40")
      (value "0.1u")
      (footprint "eagle-import:C0603K")
      (libsource (lib "eagle-import") (part "C-USC0603K"))
    )
    (comp (ref "C41")
      (value "100p")
      (footprint "eagle-import:C0603K")
      (libsource (lib "eagle-import") (part "C-USC0603K"))
    )
    (comp (ref "C42")
      (value "160p")
      (footprint "eagle-import:C0603K")
      (libsource (lib "eagle-import") (part "C-USC0603K"))
    )
    (comp (ref "C43")
      (value "180p")
      (footprint "eagle-import:C0603K")
      (libsource (lib "eagle-import") (part "C-USC0603K"))
    )
    (comp (ref "C44")
      (value "0.1u")
      (footprint "eagle-import:C0603K")
      (libsource (lib "eagle-import") (part "C-USC0603K"))
    )
    (comp (ref "C45")
      (value "100p")
      (footprint "eagle-import:C0603K")
      (libsource (lib "eagle-import") (part "C-USC0603K"))
    )
    (comp (ref "C46")
      (value "160p")
      (footprint "eagle-import:C0603K")
      (libsource (lib "eagle-import") (part "C-USC0603K"))
    )
    (comp (ref "C47")
      (value "180p")
      (footprint "eagle-import:C0603K")
      (libsource (lib "eagle-import") (part "C-USC0603K"))
    )
    (comp (ref "C48")
      (value "0.1u")
      (footprint "eagle-import:C0603K")
      (libsource (lib "eagle-import") (part "C-USC0603K"))
    )
    (comp (ref "C49")
      (value "100p")
      (footprint "eagle-import:C0603K")
      (libsource (lib "eagle-import") (part "C-USC0603K"))
    )
    (comp (ref "C50")
      (value "160p")
      (footprint "eagle-import:C0603K")
      (libsource (lib "eagle-import") (part "C-USC0603K"))
    )
    (comp (ref "C51")
      (value "180p")
      (footprint "eagle-import:C0603K")
      (libsource (lib "eagle-import") (part "C-USC0603K"))
    )
    (comp (ref "C92")
      (value "470n")
      (footprint "eagle-import:C0402K")
      (libsource (lib "eagle-import") (part "C-USC0402K"))
    )
    (comp (ref "C93")
      (value "470n")
      (footprint "eagle-import:C0402K")
      (libsource (lib "eagle-import") (part "C-USC0402K"))
    )
    (comp (ref "C94")
      (value "NFM21PS106B0J3D")
      (footprint "eagle-import:NFM21PS")
      (libsource (lib "eagle-import") (part "NFM21PS"))
    )
    (comp (ref "C95")
      (value "NFM21PS106B0J3D")
      (footprint "eagle-import:NFM21PS")
      (libsource (lib "eagle-import") (part "NFM21PS"))
    )
    (comp (ref "C96")
      (value "470n")
      (footprint "eagle-import:C0402K")
      (libsource (lib "eagle-import") (part "C-USC0402K"))
    )
    (comp (ref "C97")
      (value "470n")
      (footprint "eagle-import:C0402K")
      (libsource (lib "eagle-import") (part "C-USC0402K"))
    )
    (comp (ref "C98")
      (value "NFM21PS106B0J3D")
      (footprint "eagle-import:NFM21PS")
      (libsource (lib "eagle-import") (part "NFM21PS"))
    )
    (comp (ref "C99")
      (value "NFM21PS106B0J3D")
      (footprint "eagle-import:NFM21PS")
      (libsource (lib "eagle-import") (part "NFM21PS"))
    )
    (comp (ref "C100")
      (value "470n")
      (footprint "eagle-import:C0402K")
      (libsource (lib "eagle-import") (part "C-USC0402K"))
    )
    (comp (ref "C101")
      (value "470n")
      (footprint "eagle-import:C0402K")
      (libsource (lib "eagle-import") (part "C-USC0402K"))
    )
    (comp (ref "C102")
      (value "NFM21PS106B0J3D")
      (footprint "eagle-import:NFM21PS")
      (libsource (lib "eagle-import") (part "NFM21PS"))
    )
    (comp (ref "C103")
      (value "NFM21PS106B0J3D")
      (footprint "eagle-import:NFM21PS")
      (libsource (lib "eagle-import") (part "NFM21PS"))
    )
    (comp (ref "L16")
      (value "100n")
      (footprint "eagle-import:C1206")
      (libsource (lib "eagle-import") (part "L-US1206"))
    )
    (comp (ref "L17")
      (value "100n")
      (footprint "eagle-import:C1206")
      (libsource (lib "eagle-import") (part "L-US1206"))
    )
    (comp (ref "L18")
      (value "100n")
      (footprint "eagle-import:C1206")
      (libsource (lib "eagle-import") (part "L-US1206"))
    )
    (comp (ref "L19")
      (value "100n")
      (footprint "eagle-import:C1206")
      (libsource (lib "eagle-import") (part "L-US1206"))
    )
    (comp (ref "L20")
      (value "100n")
      (footprint "eagle-import:C1206")
      (libsource (lib "eagle-import") (part "L-US1206"))
    )
    (comp (ref "L21")
      (value "100n")
      (footprint "eagle-import:C1206")
      (libsource (lib "eagle-import") (part "L-US1206"))
    )
    (comp (ref "L22")
      (value "100n")
      (footprint "eagle-import:C1206")
      (libsource (lib "eagle-import") (part "L-US1206"))
    )
    (comp (ref "L23")
      (value "100n")
      (footprint "eagle-import:C1206")
      (libsource (lib "eagle-import") (part "L-US1206"))
    )
    (comp (ref "L24")
      (value "100n")
      (footprint "eagle-import:C1206")
      (libsource (lib "eagle-import") (part "L-US1206"))
    )
    (comp (ref "L25")
      (value "100n")
      (footprint "eagle-import:C1206")
      (libsource (lib "eagle-import") (part "L-US1206"))
    )
    (comp (ref "L26")
      (value "100n")
      (footprint "eagle-import:C1206")
      (libsource (lib "eagle-import") (part "L-US1206"))
    )
    (comp (ref "LDO_10")
      (value "TPS7A8101DRB")
      (footprint "eagle-import:DRB")
      (libsource (lib "eagle-import") (part "TPS7A8101DRB"))
    )
    (comp (ref "LDO_11")
      (value "TPS7A8101DRB")
      (footprint "eagle-import:DRB")
      (libsource (lib "eagle-import") (part "TPS7A8101DRB"))
    )
    (comp (ref "LDO_12")
      (value "TPS7A8101DRB")
      (footprint "eagle-import:DRB")
      (libsource (lib "eagle-import") (part "TPS7A8101DRB"))
    )
    (comp (ref "LNA_10")
      (value "SPF-5043Z")
      (footprint "eagle-import:SPF-5043Z")
      (libsource (lib "eagle-import") (part "SPF-5043Z"))
    )
    (comp (ref "LNA_11")
      (value "SPF-5043Z")
      (footprint "eagle-import:SPF-5043Z")
      (libsource (lib "eagle-import") (part "SPF-5043Z"))
    )
    (comp (ref "LNA_12")
      (value "SPF-5043Z")
      (footprint "eagle-import:SPF-5043Z")
      (libsource (lib "eagle-import") (part "SPF-5043Z"))
    )
    (comp (ref "R33")
      (value "10.0k")
      (footprint "eagle-import:R0603")
      (libsource (lib "eagle-import") (part "R-US_R0603"))
    )
    (comp (ref "R34")
      (value "52.3k")
      (footprint "eagle-import:R0603")
      (libsource (lib "eagle-import") (part "R-US_R0603"))
    )
    (comp (ref "R35")
      (value "10.0k")
      (footprint "eagle-import:R0603")
      (libsource (lib "eagle-import") (part "R-US_R0603"))
    )
    (comp (ref "R36")
      (value "10.0k")
      (footprint "eagle-import:R0603")
      (libsource (lib "eagle-import") (part "R-US_R0603"))
    )
    (comp (ref "R37")
      (value "52.3k")
      (footprint "eagle-import:R0603")
      (libsource (lib "eagle-import") (part "R-US_R0603"))
    )
    (comp (ref "R38")
      (value "10.0k")
      (footprint "eagle-import:R0603")
      (libsource (lib "eagle-import") (part "R-US_R0603"))
    )
    (comp (ref "R39")
      (value "10.0k")
      (footprint "eagle-import:R0603")
      (libsource (lib "eagle-import") (part "R-US_R0603"))
    )
    (comp (ref "R40")
      (value "52.3k")
      (footprint "eagle-import:R0603")
      (libsource (lib "eagle-import") (part "R-US_R0603"))
    )
    (comp (ref "R41")
      (value "10.0k")
      (footprint "eagle-import:R0603")
      (libsource (lib "eagle-import") (part "R-US_R0603"))
    )
    (comp (ref "SAW_13")
      (value "S511214")
      (footprint "eagle-import:S511214")
      (libsource (lib "eagle-import") (part "S511214"))
    )
    (comp (ref "SAW_14")
      (value "S511214")
      (footprint "eagle-import:S511214")
      (libsource (lib "eagle-import") (part "S511214"))
    )
    (comp (ref "SAW_15")
      (value "S511214")
      (footprint "eagle-import:S511214")
      (libsource (lib "eagle-import") (part "S511214"))
    )
    (comp (ref "SAW_16")
      (value "S511214")
      (footprint "eagle-import:S511214")
      (libsource (lib "eagle-import") (part "S511214"))
    )
    (comp (ref "TP_10")
      (value "TPTP20SQ")
      (footprint "eagle-import:TP20SQ")
      (libsource (lib "eagle-import") (part "TPTP20SQ"))
    )
    (comp (ref "TP_11")
      (value "TPTP20SQ")
      (footprint "eagle-import:TP20SQ")
      (libsource (lib "eagle-import") (part "TPTP20SQ"))
    )
    (comp (ref "TP_12")
      (value "TPTP20SQ")
      (footprint "eagle-import:TP20SQ")
      (libsource (lib "eagle-import") (part "TPTP20SQ"))
    )
    (comp (ref "X25")
      (value "0733660061")
      (footprint "eagle-import:BU-SMA-V")
      (libsource (lib "eagle-import") (part "BU-SMA-V"))
    )
    (comp (ref "X26")
      (value "0733660061")
      (footprint "eagle-import:BU-SMA-V")
      (libsource (lib "eagle-import") (part "BU-SMA-V"))
    )
    (comp (ref "X27")
      (value "0733660061")
      (footprint "eagle-import:BU-SMA-V")
      (libsource (lib "eagle-import") (part "BU-SMA-V"))
    )
    (comp (ref "X28")
      (value "0733660061")
      (footprint "eagle-import:BU-SMA-V")
      (libsource (lib "eagle-import") (part "BU-SMA-V"))
    )
    (comp (ref "X29")
      (value "0733660061")
      (footprint "eagle-import:BU-SMA-V")
      (libsource (lib "eagle-import") (part "BU-SMA-V"))
    )
    (comp (ref "X30")
      (value "0733660061")
      (footprint "eagle-import:BU-SMA-V")
      (libsource (lib "eagle-import") (part "BU-SMA-V"))
    )
    (comp (ref "X31")
      (value "0733660061")
      (footprint "eagle-import:BU-SMA-V")
      (libsource (lib "eagle-import") (part "BU-SMA-V"))
    )
    (comp (ref "X32")
      (value "0733660061")
      (footprint "eagle-import:BU-SMA-V")
      (libsource (lib "eagle-import") (part "BU-SMA-V"))
    )
  )
  (nets
    (net (code "1") (name "+5V3") (class "Default")
      (node (ref "C102") (pin "IN") (pinfunction "IN_IN") (pintype "bidirectional"))
      (node (ref "C459") (pin "OUT") (pinfunction "OUT_OUT") (pintype "bidirectional"))
      (node (ref "C55") (pin "IN") (pinfunction "IN_IN") (pintype "bidirectional"))
      (node (ref "C60") (pin "IN") (pinfunction "IN_IN") (pintype "bidirectional"))
      (node (ref "C64") (pin "IN") (pinfunction "IN_IN") (pintype "bidirectional"))
      (node (ref "C68") (pin "IN") (pinfunction "IN_IN") (pintype "bidirectional"))
      (node (ref "C74") (pin "IN") (pinfunction "IN_IN") (pintype "bidirectional"))
      (node (ref "C78") (pin "IN") (pinfunction "IN_IN") (pintype "bidirectional"))
      (node (ref "C82") (pin "IN") (pinfunction "IN_IN") (pintype "bidirectional"))
      (node (ref "C86") (pin "IN") (pinfunction "IN_IN") (pintype "bidirectional"))
      (node (ref "C90") (pin "IN") (pinfunction "IN_IN") (pintype "bidirectional"))
      (node (ref "C94") (pin "IN") (pinfunction "IN_IN") (pintype "bidirectional"))
      (node (ref "C98") (pin "IN") (pinfunction "IN_IN") (pintype "bidirectional"))
      (node (ref "IC58") (pin "27") (pinfunction "SENSE+_27") (pintype "bidirectional"))
      (node (ref "R1") (pin "1") (pinfunction "1_1") (pintype "passive"))
      (node (ref "R11") (pin "1") (pinfunction "1_1") (pintype "passive"))
      (node (ref "R15") (pin "1") (pinfunction "1_1") (pintype "passive"))
      (node (ref "R201") (pin "2") (pinfunction "2_2") (pintype "passive"))
      (node (ref "R21") (pin "1") (pinfunction "1_1") (pintype "passive"))
      (node (ref "R24") (pin "1") (pinfunction "1_1") (pintype "passive"))
      (node (ref "R27") (pin "1") (pinfunction "1_1") (pintype "passive"))
      (node (ref "R30") (pin "1") (pinfunction "1_1") (pintype "passive"))
      (node (ref "R33") (pin "1") (pinfunction "1_1") (pintype "passive"))
      (node (ref "R36") (pin "1") (pinfunction "1_1") (pintype "passive"))
      (node (ref "R39") (pin "1") (pinfunction "1_1") (pintype "passive"))
      (node (ref "R5") (pin "1") (pinfunction "1_1") (pintype "passive"))
      (node (ref "R8") (pin "1") (pinfunction "1_1") (pintype "passive"))
    )
    (net (code "2") (name "+5V3_INH") (class "Default")
      (node (ref "Q2") (pin "3") (pinfunction "G_3") (pintype "passive"))
      (node (ref "R13") (pin "1") (pinfunction "1_1") (pintype "passive"))
    )
    (net (code "3") (name "+13.8V_TPS") (class "Default")
      (node (ref "L31") (pin "1") (pinfunction "1_1") (pintype "passive"))
    )
    (net (code "4") (name "GND") (class "Default")
      (node (ref "C10") (pin "2") (pinfunction "2_2") (pintype "passive"))
      (node (ref "C100") (pin "2") (pinfunction "2_2") (pintype "passive"))
      (node (ref "C102") (pin "GND1") (pinfunction "GND_GND1") (pintype "bidirectional"))
      (node (ref "C102") (pin "GND2") (pinfunction "GND_GND2") (pintype "bidirectional"))
      (node (ref "C102") (pin "GND3") (pinfunction "GND_GND3") (pintype "bidirectional"))
      (node (ref "C102") (pin "GND4") (pinfunction "GND_GND4") (pintype "bidirectional"))
      (node (ref "C102") (pin "GND5") (pinfunction "GND_GND5") (pintype "bidirectional"))
      (node (ref "C102") (pin "GND6") (pinfunction "GND_GND6") (pintype "bidirectional"))
      (node (ref "C102") (pin "GND7") (pinfunction "GND_GND7") (pintype "bidirectional"))
      (node (ref "C102") (pin "GND8") (pinfunction "GND_GND8") (pintype "bidirectional"))
      (node (ref "C103") (pin "GND1") (pinfunction "GND_GND1") (pintype "bidirectional"))
      (node (ref "C103") (pin "GND2") (pinfunction "GND_GND2") (pintype "bidirectional"))
      (node (ref "C103") (pin "GND3") (pinfunction "GND_GND3") (pintype "bidirectional"))
      (node (ref "C103") (pin "GND4") (pinfunction "GND_GND4") (pintype "bidirectional"))
      (node (ref "C103") (pin "GND5") (pinfunction "GND_GND5") (pintype "bidirectional"))
      (node (ref "C103") (pin "GND6") (pinfunction "GND_GND6") (pintype "bidirectional"))
      (node (ref "C103") (pin "GND7") (pinfunction "GND_GND7") (pintype "bidirectional"))
      (node (ref "C103") (pin "GND8") (pinfunction "GND_GND8") (pintype "bidirectional"))
      (node (ref "C11") (pin "2") (pinfunction "2_2") (pintype "passive"))
      (node (ref "C15") (pin "2") (pinfunction "2_2") (pintype "passive"))
      (node (ref "C16") (pin "2") (pinfunction "2_2") (pintype "passive"))
      (node (ref "C19") (pin "2") (pinfunction "2_2") (pintype "passive"))
      (node (ref "C2") (pin "2") (pinfunction "2_2") (pintype "passive"))
      (node (ref "C20") (pin "2") (pinfunction "2_2") (pintype "passive"))
      (node (ref "C23") (pin "2") (pinfunction "2_2") (pintype "passive"))
      (node (ref "C24") (pin "2") (pinfunction "2_2") (pintype "passive"))
      (node (ref "C27") (pin "2") (pinfunction "2_2") (pintype "passive"))
      (node (ref "C28") (pin "2") (pinfunction "2_2") (pintype "passive"))
      (node (ref "C3") (pin "2") (pinfunction "2_2") (pintype "passive"))
      (node (ref "C31") (pin "2") (pinfunction "2_2") (pintype "passive"))
      (node (ref "C32") (pin "2") (pinfunction "2_2") (pintype "passive"))
      (node (ref "C35") (pin "2") (pinfunction "2_2") (pintype "passive"))
      (node (ref "C36") (pin "2") (pinfunction "2_2") (pintype "passive"))
      (node (ref "C40") (pin "2") (pinfunction "2_2") (pintype "passive"))
      (node (ref "C41") (pin "2") (pinfunction "2_2") (pintype "passive"))
      (node (ref "C44") (pin "2") (pinfunction "2_2") (pintype "passive"))
      (node (ref "C45") (pin "2") (pinfunction "2_2") (pintype "passive"))
      (node (ref "C459") (pin "GND1") (pinfunction "GND_GND1") (pintype "bidirectional"))
      (node (ref "C459") (pin "GND2") (pinfunction "GND_GND2") (pintype "bidirectional"))
      (node (ref "C459") (pin "GND3") (pinfunction "GND_GND3") (pintype "bidirectional"))
      (node (ref "C459") (pin "GND4") (pinfunction "GND_GND4") (pintype "bidirectional"))
      (node (ref "C459") (pin "GND5") (pinfunction "GND_GND5") (pintype "bidirectional"))
      (node (ref "C48") (pin "2") (pinfunction "2_2") (pintype "passive"))
      (node (ref "C481") (pin "2") (pinfunction "2_2") (pintype "passive"))
      (node (ref "C482") (pin "2") (pinfunction "2_2") (pintype "passive"))
      (node (ref "C483") (pin "-") (pinfunction "-_-") (pintype "passive"))
      (node (ref "C484") (pin "-") (pinfunction "-_-") (pintype "passive"))
      (node (ref "C489") (pin "2") (pinfunction "2_2") (pintype "passive"))
      (node (ref "C49") (pin "2") (pinfunction "2_2") (pintype "passive"))
      (node (ref "C490") (pin "2") (pinfunction "2_2") (pintype "passive"))
      (node (ref "C491") (pin "2") (pinfunction "2_2") (pintype "passive"))
      (node (ref "C492") (pin "2") (pinfunction "2_2") (pintype "passive"))
      (node (ref "C493") (pin "2") (pinfunction "2_2") (pintype "passive"))
      (node (ref "C500") (pin "GND@1") (pinfunction "GND_GND@1") (pintype "power_in"))
      (node (ref "C500") (pin "GND@2") (pinfunction "GND_GND@2") (pintype "power_in"))
      (node (ref "C53") (pin "2") (pinfunction "2_2") (pintype "passive"))
      (node (ref "C55") (pin "GND1") (pinfunction "GND_GND1") (pintype "bidirectional"))
      (node (ref "C55") (pin "GND2") (pinfunction "GND_GND2") (pintype "bidirectional"))
      (node (ref "C55") (pin "GND3") (pinfunction "GND_GND3") (pintype "bidirectional"))
      (node (ref "C55") (pin "GND4") (pinfunction "GND_GND4") (pintype "bidirectional"))
      (node (ref "C55") (pin "GND5") (pinfunction "GND_GND5") (pintype "bidirectional"))
      (node (ref "C55") (pin "GND6") (pinfunction "GND_GND6") (pintype "bidirectional"))
      (node (ref "C55") (pin "GND7") (pinfunction "GND_GND7") (pintype "bidirectional"))
      (node (ref "C55") (pin "GND8") (pinfunction "GND_GND8") (pintype "bidirectional"))
      (node (ref "C56") (pin "GND1") (pinfunction "GND_GND1") (pintype "bidirectional"))
      (node (ref "C56") (pin "GND2") (pinfunction "GND_GND2") (pintype "bidirectional"))
      (node (ref "C56") (pin "GND3") (pinfunction "GND_GND3") (pintype "bidirectional"))
      (node (ref "C56") (pin "GND4") (pinfunction "GND_GND4") (pintype "bidirectional"))
      (node (ref "C56") (pin "GND5") (pinfunction "GND_GND5") (pintype "bidirectional"))
      (node (ref "C56") (pin "GND6") (pinfunction "GND_GND6") (pintype "bidirectional"))
      (node (ref "C56") (pin "GND7") (pinfunction "GND_GND7") (pintype "bidirectional"))
      (node (ref "C56") (pin "GND8") (pinfunction "GND_GND8") (pintype "bidirectional"))
      (node (ref "C58") (pin "2") (pinfunction "2_2") (pintype "passive"))
      (node (ref "C6") (pin "2") (pinfunction "2_2") (pintype "passive"))
      (node (ref "C60") (pin "GND1") (pinfunction "GND_GND1") (pintype "bidirectional"))
      (node (ref "C60") (pin "GND2") (pinfunction "GND_GND2") (pintype "bidirectional"))
      (node (ref "C60") (pin "GND3") (pinfunction "GND_GND3") (pintype "bidirectional"))
      (node (ref "C60") (pin "GND4") (pinfunction "GND_GND4") (pintype "bidirectional"))
      (node (ref "C60") (pin "GND5") (pinfunction "GND_GND5") (pintype "bidirectional"))
      (node (ref "C60") (pin "GND6") (pinfunction "GND_GND6") (pintype "bidirectional"))
      (node (ref "C60") (pin "GND7") (pinfunction "GND_GND7") (pintype "bidirectional"))
      (node (ref "C60") (pin "GND8") (pinfunction "GND_GND8") (pintype "bidirectional"))
      (node (ref "C61") (pin "GND1") (pinfunction "GND_GND1") (pintype "bidirectional"))
      (node (ref "C61") (pin "GND2") (pinfunction "GND_GND2") (pintype "bidirectional"))
      (node (ref "C61") (pin "GND3") (pinfunction "GND_GND3") (pintype "bidirectional"))
      (node (ref "C61") (pin "GND4") (pinfunction "GND_GND4") (pintype "bidirectional"))
      (node (ref "C61") (pin "GND5") (pinfunction "GND_GND5") (pintype "bidirectional"))
      (node (ref "C61") (pin "GND6") (pinfunction "GND_GND6") (pintype "bidirectional"))
      (node (ref "C61") (pin "GND7") (pinfunction "GND_GND7") (pintype "bidirectional"))
      (node (ref "C61") (pin "GND8") (pinfunction "GND_GND8") (pintype "bidirectional"))
      (node (ref "C62") (pin "2") (pinfunction "2_2") (pintype "passive"))
      (node (ref "C64") (pin "GND1") (pinfunction "GND_GND1") (pintype "bidirectional"))
      (node (ref "C64") (pin "GND2") (pinfunction "GND_GND2") (pintype "bidirectional"))
      (node (ref "C64") (pin "GND3") (pinfunction "GND_GND3") (pintype "bidirectional"))
      (node (ref "C64") (pin "GND4") (pinfunction "GND_GND4") (pintype "bidirectional"))
      (node (ref "C64") (pin "GND5") (pinfunction "GND_GND5") (pintype "bidirectional"))
      (node (ref "C64") (pin "GND6") (pinfunction "GND_GND6") (pintype "bidirectional"))
      (node (ref "C64") (pin "GND7") (pinfunction "GND_GND7") (pintype "bidirectional"))
      (node (ref "C64") (pin "GND8") (pinfunction "GND_GND8") (pintype "bidirectional"))
      (node (ref "C65") (pin "GND1") (pinfunction "GND_GND1") (pintype "bidirectional"))
      (node (ref "C65") (pin "GND2") (pinfunction "GND_GND2") (pintype "bidirectional"))
      (node (ref "C65") (pin "GND3") (pinfunction "GND_GND3") (pintype "bidirectional"))
      (node (ref "C65") (pin "GND4") (pinfunction "GND_GND4") (pintype "bidirectional"))
      (node (ref "C65") (pin "GND5") (pinfunction "GND_GND5") (pintype "bidirectional"))
      (node (ref "C65") (pin "GND6") (pinfunction "GND_GND6") (pintype "bidirectional"))
      (node (ref "C65") (pin "GND7") (pinfunction "GND_GND7") (pintype "bidirectional"))
      (node (ref "C65") (pin "GND8") (pinfunction "GND_GND8") (pintype "bidirectional"))
      (node (ref "C66") (pin "2") (pinfunction "2_2") (pintype "passive"))
      (node (ref "C68") (pin "GND1") (pinfunction "GND_GND1") (pintype "bidirectional"))
      (node (ref "C68") (pin "GND2") (pinfunction "GND_GND2") (pintype "bidirectional"))
      (node (ref "C68") (pin "GND3") (pinfunction "GND_GND3") (pintype "bidirectional"))
      (node (ref "C68") (pin "GND4") (pinfunction "GND_GND4") (pintype "bidirectional"))
      (node (ref "C68") (pin "GND5") (pinfunction "GND_GND5") (pintype "bidirectional"))
      (node (ref "C68") (pin "GND6") (pinfunction "GND_GND6") (pintype "bidirectional"))
      (node (ref "C68") (pin "GND7") (pinfunction "GND_GND7") (pintype "bidirectional"))
      (node (ref "C68") (pin "GND8") (pinfunction "GND_GND8") (pintype "bidirectional"))
      (node (ref "C69") (pin "GND1") (pinfunction "GND_GND1") (pintype "bidirectional"))
      (node (ref "C69") (pin "GND2") (pinfunction "GND_GND2") (pintype "bidirectional"))
      (node (ref "C69") (pin "GND3") (pinfunction "GND_GND3") (pintype "bidirectional"))
      (node (ref "C69") (pin "GND4") (pinfunction "GND_GND4") (pintype "bidirectional"))
      (node (ref "C69") (pin "GND5") (pinfunction "GND_GND5") (pintype "bidirectional"))
      (node (ref "C69") (pin "GND6") (pinfunction "GND_GND6") (pintype "bidirectional"))
      (node (ref "C69") (pin "GND7") (pinfunction "GND_GND7") (pintype "bidirectional"))
      (node (ref "C69") (pin "GND8") (pinfunction "GND_GND8") (pintype "bidirectional"))
      (node (ref "C7") (pin "2") (pinfunction "2_2") (pintype "passive"))
      (node (ref "C70") (pin "2") (pinfunction "2_2") (pintype "passive"))
      (node (ref "C74") (pin "GND1") (pinfunction "GND_GND1") (pintype "bidirectional"))
      (node (ref "C74") (pin "GND2") (pinfunction "GND_GND2") (pintype "bidirectional"))
      (node (ref "C74") (pin "GND3") (pinfunction "GND_GND3") (pintype "bidirectional"))
      (node (ref "C74") (pin "GND4") (pinfunction "GND_GND4") (pintype "bidirectional"))
      (node (ref "C74") (pin "GND5") (pinfunction "GND_GND5") (pintype "bidirectional"))
      (node (ref "C74") (pin "GND6") (pinfunction "GND_GND6") (pintype "bidirectional"))
      (node (ref "C74") (pin "GND7") (pinfunction "GND_GND7") (pintype "bidirectional"))
      (node (ref "C74") (pin "GND8") (pinfunction "GND_GND8") (pintype "bidirectional"))
      (node (ref "C75") (pin "GND1") (pinfunction "GND_GND1") (pintype "bidirectional"))
      (node (ref "C75") (pin "GND2") (pinfunction "GND_GND2") (pintype "bidirectional"))
      (node (ref "C75") (pin "GND3") (pinfunction "GND_GND3") (pintype "bidirectional"))
      (node (ref "C75") (pin "GND4") (pinfunction "GND_GND4") (pintype "bidirectional"))
      (node (ref "C75") (pin "GND5") (pinfunction "GND_GND5") (pintype "bidirectional"))
      (node (ref "C75") (pin "GND6") (pinfunction "GND_GND6") (pintype "bidirectional"))
      (node (ref "C75") (pin "GND7") (pinfunction "GND_GND7") (pintype "bidirectional"))
      (node (ref "C75") (pin "GND8") (pinfunction "GND_GND8") (pintype "bidirectional"))
      (node (ref "C76") (pin "2") (pinfunction "2_2") (pintype "passive"))
      (node (ref "C78") (pin "GND1") (pinfunction "GND_GND1") (pintype "bidirectional"))
      (node (ref "C78") (pin "GND2") (pinfunction "GND_GND2") (pintype "bidirectional"))
      (node (ref "C78") (pin "GND3") (pinfunction "GND_GND3") (pintype "bidirectional"))
      (node (ref "C78") (pin "GND4") (pinfunction "GND_GND4") (pintype "bidirectional"))
      (node (ref "C78") (pin "GND5") (pinfunction "GND_GND5") (pintype "bidirectional"))
      (node (ref "C78") (pin "GND6") (pinfunction "GND_GND6") (pintype "bidirectional"))
      (node (ref "C78") (pin "GND7") (pinfunction "GND_GND7") (pintype "bidirectional"))
      (node (ref "C78") (pin "GND8") (pinfunction "GND_GND8") (pintype "bidirectional"))
      (node (ref "C79") (pin "GND1") (pinfunction "GND_GND1") (pintype "bidirectional"))
      (node (ref "C79") (pin "GND2") (pinfunction "GND_GND2") (pintype "bidirectional"))
      (node (ref "C79") (pin "GND3") (pinfunction "GND_GND3") (pintype "bidirectional"))
      (node (ref "C79") (pin "GND4") (pinfunction "GND_GND4") (pintype "bidirectional"))
      (node (ref "C79") (pin "GND5") (pinfunction "GND_GND5") (pintype "bidirectional"))
      (node (ref "C79") (pin "GND6") (pinfunction "GND_GND6") (pintype "bidirectional"))
      (node (ref "C79") (pin "GND7") (pinfunction "GND_GND7") (pintype "bidirectional"))
      (node (ref "C79") (pin "GND8") (pinfunction "GND_GND8") (pintype "bidirectional"))
      (node (ref "C80") (pin "2") (pinfunction "2_2") (pintype "passive"))
      (node (ref "C82") (pin "GND1") (pinfunction "GND_GND1") (pintype "bidirectional"))
      (node (ref "C82") (pin "GND2") (pinfunction "GND_GND2") (pintype "bidirectional"))
      (node (ref "C82") (pin "GND3") (pinfunction "GND_GND3") (pintype "bidirectional"))
      (node (ref "C82") (pin "GND4") (pinfunction "GND_GND4") (pintype "bidirectional"))
      (node (ref "C82") (pin "GND5") (pinfunction "GND_GND5") (pintype "bidirectional"))
      (node (ref "C82") (pin "GND6") (pinfunction "GND_GND6") (pintype "bidirectional"))
      (node (ref "C82") (pin "GND7") (pinfunction "GND_GND7") (pintype "bidirectional"))
      (node (ref "C82") (pin "GND8") (pinfunction "GND_GND8") (pintype "bidirectional"))
      (node (ref "C83") (pin "GND1") (pinfunction "GND_GND1") (pintype "bidirectional"))
      (node (ref "C83") (pin "GND2") (pinfunction "GND_GND2") (pintype "bidirectional"))
      (node (ref "C83") (pin "GND3") (pinfunction "GND_GND3") (pintype "bidirectional"))
      (node (ref "C83") (pin "GND4") (pinfunction "GND_GND4") (pintype "bidirectional"))
      (node (ref "C83") (pin "GND5") (pinfunction "GND_GND5") (pintype "bidirectional"))
      (node (ref "C83") (pin "GND6") (pinfunction "GND_GND6") (pintype "bidirectional"))
      (node (ref "C83") (pin "GND7") (pinfunction "GND_GND7") (pintype "bidirectional"))
      (node (ref "C83") (pin "GND8") (pinfunction "GND_GND8") (pintype "bidirectional"))
      (node (ref "C84") (pin "2") (pinfunction "2_2") (pintype "passive"))
      (node (ref "C86") (pin "GND1") (pinfunction "GND_GND1") (pintype "bidirectional"))
      (node (ref "C86") (pin "GND2") (pinfunction "GND_GND2") (pintype "bidirectional"))
      (node (ref "C86") (pin "GND3") (pinfunction "GND_GND3") (pintype "bidirectional"))
      (node (ref "C86") (pin "GND4") (pinfunction "GND_GND4") (pintype "bidirectional"))
      (node (ref "C86") (pin "GND5") (pinfunction "GND_GND5") (pintype "bidirectional"))
      (node (ref "C86") (pin "GND6") (pinfunction "GND_GND6") (pintype "bidirectional"))
      (node (ref "C86") (pin "GND7") (pinfunction "GND_GND7") (pintype "bidirectional"))
      (node (ref "C86") (pin "GND8") (pinfunction "GND_GND8") (pintype "bidirectional"))
      (node (ref "C87") (pin "GND1") (pinfunction "GND_GND1") (pintype "bidirectional"))
      (node (ref "C87") (pin "GND2") (pinfunction "GND_GND2") (pintype "bidirectional"))
      (node (ref "C87") (pin "GND3") (pinfunction "GND_GND3") (pintype "bidirectional"))
      (node (ref "C87") (pin "GND4") (pinfunction "GND_GND4") (pintype "bidirectional"))
      (node (ref "C87") (pin "GND5") (pinfunction "GND_GND5") (pintype "bidirectional"))
      (node (ref "C87") (pin "GND6") (pinfunction "GND_GND6") (pintype "bidirectional"))
      (node (ref "C87") (pin "GND7") (pinfunction "GND_GND7") (pintype "bidirectional"))
      (node (ref "C87") (pin "GND8") (pinfunction "GND_GND8") (pintype "bidirectional"))
      (node (ref "C88") (pin "2") (pinfunction "2_2") (pintype "passive"))
      (node (ref "C90") (pin "GND1") (pinfunction "GND_GND1") (pintype "bidirectional"))
      (node (ref "C90") (pin "GND2") (pinfunction "GND_GND2") (pintype "bidirectional"))
      (node (ref "C90") (pin "GND3") (pinfunction "GND_GND3") (pintype "bidirectional"))
      (node (ref "C90") (pin "GND4") (pinfunction "GND_GND4") (pintype "bidirectional"))
      (node (ref "C90") (pin "GND5") (pinfunction "GND_GND5") (pintype "bidirectional"))
      (node (ref "C90") (pin "GND6") (pinfunction "GND_GND6") (pintype "bidirectional"))
      (node (ref "C90") (pin "GND7") (pinfunction "GND_GND7") (pintype "bidirectional"))
      (node (ref "C90") (pin "GND8") (pinfunction "GND_GND8") (pintype "bidirectional"))
      (node (ref "C91") (pin "GND1") (pinfunction "GND_GND1") (pintype "bidirectional"))
      (node (ref "C91") (pin "GND2") (pinfunction "GND_GND2") (pintype "bidirectional"))
      (node (ref "C91") (pin "GND3") (pinfunction "GND_GND3") (pintype "bidirectional"))
      (node (ref "C91") (pin "GND4") (pinfunction "GND_GND4") (pintype "bidirectional"))
      (node (ref "C91") (pin "GND5") (pinfunction "GND_GND5") (pintype "bidirectional"))
      (node (ref "C91") (pin "GND6") (pinfunction "GND_GND6") (pintype "bidirectional"))
      (node (ref "C91") (pin "GND7") (pinfunction "GND_GND7") (pintype "bidirectional"))
      (node (ref "C91") (pin "GND8") (pinfunction "GND_GND8") (pintype "bidirectional"))
      (node (ref "C92") (pin "2") (pinfunction "2_2") (pintype "passive"))
      (node (ref "C94") (pin "GND1") (pinfunction "GND_GND1") (pintype "bidirectional"))
      (node (ref "C94") (pin "GND2") (pinfunction "GND_GND2") (pintype "bidirectional"))
      (node (ref "C94") (pin "GND3") (pinfunction "GND_GND3") (pintype "bidirectional"))
      (node (ref "C94") (pin "GND4") (pinfunction "GND_GND4") (pintype "bidirectional"))
      (node (ref "C94") (pin "GND5") (pinfunction "GND_GND5") (pintype "bidirectional"))
      (node (ref "C94") (pin "GND6") (pinfunction "GND_GND6") (pintype "bidirectional"))
      (node (ref "C94") (pin "GND7") (pinfunction "GND_GND7") (pintype "bidirectional"))
      (node (ref "C94") (pin "GND8") (pinfunction "GND_GND8") (pintype "bidirectional"))
      (node (ref "C95") (pin "GND1") (pinfunction "GND_GND1") (pintype "bidirectional"))
      (node (ref "C95") (pin "GND2") (pinfunction "GND_GND2") (pintype "bidirectional"))
      (node (ref "C95") (pin "GND3") (pinfunction "GND_GND3") (pintype "bidirectional"))
      (node (ref "C95") (pin "GND4") (pinfunction "GND_GND4") (pintype "bidirectional"))
      (node (ref "C95") (pin "GND5") (pinfunction "GND_GND5") (pintype "bidirectional"))
      (node (ref "C95") (pin "GND6") (pinfunction "GND_GND6") (pintype "bidirectional"))
      (node (ref "C95") (pin "GND7") (pinfunction "GND_GND7") (pintype "bidirectional"))
      (node (ref "C95") (pin "GND8") (pinfunction "GND_GND8") (pintype "bidirectional"))
      (node (ref "C96") (pin "2") (pinfunction "2_2") (pintype "passive"))
      (node (ref "C98") (pin "GND1") (pinfunction "GND_GND1") (pintype "bidirectional"))
      (node (ref "C98") (pin "GND2") (pinfunction "GND_GND2") (pintype "bidirectional"))
      (node (ref "C98") (pin "GND3") (pinfunction "GND_GND3") (pintype "bidirectional"))
      (node (ref "C98") (pin "GND4") (pinfunction "GND_GND4") (pintype "bidirectional"))
      (node (ref "C98") (pin "GND5") (pinfunction "GND_GND5") (pintype "bidirectional"))
      (node (ref "C98") (pin "GND6") (pinfunction "GND_GND6") (pintype "bidirectional"))
      (node (ref "C98") (pin "GND7") (pinfunction "GND_GND7") (pintype "bidirectional"))
      (node (ref "C98") (pin "GND8") (pinfunction "GND_GND8") (pintype "bidirectional"))
      (node (ref "C99") (pin "GND1") (pinfunction "GND_GND1") (pintype "bidirectional"))
      (node (ref "C99") (pin "GND2") (pinfunction "GND_GND2") (pintype "bidirectional"))
      (node (ref "C99") (pin "GND3") (pinfunction "GND_GND3") (pintype "bidirectional"))
      (node (ref "C99") (pin "GND4") (pinfunction "GND_GND4") (pintype "bidirectional"))
      (node (ref "C99") (pin "GND5") (pinfunction "GND_GND5") (pintype "bidirectional"))
      (node (ref "C99") (pin "GND6") (pinfunction "GND_GND6") (pintype "bidirectional"))
      (node (ref "C99") (pin "GND7") (pinfunction "GND_GND7") (pintype "bidirectional"))
      (node (ref "C99") (pin "GND8") (pinfunction "GND_GND8") (pintype "bidirectional"))
      (node (ref "IC58") (pin "2") (pinfunction "AGND_2") (pintype "bidirectional"))
      (node (ref "IC58") (pin "20") (pinfunction "PGND_20") (pintype "bidirectional"))
      (node (ref "IC58") (pin "21") (pinfunction "PGND_21") (pintype "bidirectional"))
      (node (ref "IC58") (pin "23") (pinfunction "AGND_23") (pintype "bidirectional"))
      (node (ref "IC58") (pin "29") (pinfunction "STSEL_29") (pintype "bidirectional"))
      (node (ref "IC58") (pin "31") (pinfunction "PGND_31") (pintype "bidirectional"))
      (node (ref "IC58") (pin "32") (pinfunction "PGND_32") (pintype "bidirectional"))
      (node (ref "IC58") (pin "33") (pinfunction "PGND_33") (pintype "bidirectional"))
      (node (ref "L16") (pin "2") (pinfunction "2_2") (pintype "passive"))
      (node (ref "L17") (pin "2") (pinfunction "2_2") (pintype "passive"))
      (node (ref "L19") (pin "2") (pinfunction "2_2") (pintype "passive"))
      (node (ref "L2") (pin "1") (pinfunction "1_1") (pintype "passive"))
      (node (ref "L20") (pin "2") (pinfunction "2_2") (pintype "passive"))
      (node (ref "L22") (pin "2") (pinfunction "2_2") (pintype "passive"))
      (node (ref "L23") (pin "2") (pinfunction "2_2") (pintype "passive"))
      (node (ref "L25") (pin "2") (pinfunction "2_2") (pintype "passive"))
      (node (ref "L26") (pin "2") (pinfunction "2_2") (pintype "passive"))
      (node (ref "L3") (pin "1") (pinfunction "1_1") (pintype "passive"))
      (node (ref "L5") (pin "1") (pinfunction "1_1") (pintype "passive"))
      (node (ref "L6") (pin "1") (pinfunction "1_1") (pintype "passive"))
      (node (ref "L8") (pin "1") (pinfunction "1_1") (pintype "passive"))
      (node (ref "L9") (pin "1") (pinfunction "1_1") (pintype "passive"))
      (node (ref "LDO_1") (pin "4") (pinfunction "GND_4") (pintype "bidirectional"))
      (node (ref "LDO_1") (pin "P1") (pinfunction "GND_P1") (pintype "bidirectional"))
      (node (ref "LDO_1") (pin "P2") (pinfunction "GND_P2") (pintype "bidirectional"))
      (node (ref "LDO_1") (pin "P3") (pinfunction "GND_P3") (pintype "bidirectional"))
      (node (ref "LDO_1") (pin "P4") (pinfunction "GND_P4") (pintype "bidirectional"))
      (node (ref "LDO_1") (pin "P5") (pinfunction "GND_P5") (pintype "bidirectional"))
      (node (ref "LDO_1") (pin "PAD") (pinfunction "GND_PAD") (pintype "bidirectional"))
      (node (ref "LDO_10") (pin "4") (pinfunction "GND_4") (pintype "bidirectional"))
      (node (ref "LDO_10") (pin "P1") (pinfunction "GND_P1") (pintype "bidirectional"))
      (node (ref "LDO_10") (pin "P2") (pinfunction "GND_P2") (pintype "bidirectional"))
      (node (ref "LDO_10") (pin "P3") (pinfunction "GND_P3") (pintype "bidirectional"))
      (node (ref "LDO_10") (pin "P4") (pinfunction "GND_P4") (pintype "bidirectional"))
      (node (ref "LDO_10") (pin "P5") (pinfunction "GND_P5") (pintype "bidirectional"))
      (node (ref "LDO_10") (pin "PAD") (pinfunction "GND_PAD") (pintype "bidirectional"))
      (node (ref "LDO_11") (pin "4") (pinfunction "GND_4") (pintype "bidirectional"))
      (node (ref "LDO_11") (pin "P1") (pinfunction "GND_P1") (pintype "bidirectional"))
      (node (ref "LDO_11") (pin "P2") (pinfunction "GND_P2") (pintype "bidirectional"))
      (node (ref "LDO_11") (pin "P3") (pinfunction "GND_P3") (pintype "bidirectional"))
      (node (ref "LDO_11") (pin "P4") (pinfunction "GND_P4") (pintype "bidirectional"))
      (node (ref "LDO_11") (pin "P5") (pinfunction "GND_P5") (pintype "bidirectional"))
      (node (ref "LDO_11") (pin "PAD") (pinfunction "GND_PAD") (pintype "bidirectional"))
      (node (ref "LDO_12") (pin "4") (pinfunction "GND_4") (pintype "bidirectional"))
      (node (ref "LDO_12") (pin "P1") (pinfunction "GND_P1") (pintype "bidirectional"))
      (node (ref "LDO_12") (pin "P2") (pinfunction "GND_P2") (pintype "bidirectional"))
      (node (ref "LDO_12") (pin "P3") (pinfunction "GND_P3") (pintype "bidirectional"))
      (node (ref "LDO_12") (pin "P4") (pinfunction "GND_P4") (pintype "bidirectional"))
      (node (ref "LDO_12") (pin "P5") (pinfunction "GND_P5") (pintype "bidirectional"))
      (node (ref "LDO_12") (pin "PAD") (pinfunction "GND_PAD") (pintype "bidirectional"))
      (node (ref "LDO_2") (pin "4") (pinfunction "GND_4") (pintype "bidirectional"))
      (node (ref "LDO_2") (pin "P1") (pinfunction "GND_P1") (pintype "bidirectional"))
      (node (ref "LDO_2") (pin "P2") (pinfunction "GND_P2") (pintype "bidirectional"))
      (node (ref "LDO_2") (pin "P3") (pinfunction "GND_P3") (pintype "bidirectional"))
      (node (ref "LDO_2") (pin "P4") (pinfunction "GND_P4") (pintype "bidirectional"))
      (node (ref "LDO_2") (pin "P5") (pinfunction "GND_P5") (pintype "bidirectional"))
      (node (ref "LDO_2") (pin "PAD") (pinfunction "GND_PAD") (pintype "bidirectional"))
      (node (ref "LDO_3") (pin "4") (pinfunction "GND_4") (pintype "bidirectional"))
      (node (ref "LDO_3") (pin "P1") (pinfunction "GND_P1") (pintype "bidirectional"))
      (node (ref "LDO_3") (pin "P2") (pinfunction "GND_P2") (pintype "bidirectional"))
      (node (ref "LDO_3") (pin "P3") (pinfunction "GND_P3") (pintype "bidirectional"))
      (node (ref "LDO_3") (pin "P4") (pinfunction "GND_P4") (pintype "bidirectional"))
      (node (ref "LDO_3") (pin "P5") (pinfunction "GND_P5") (pintype "bidirectional"))
      (node (ref "LDO_3") (pin "PAD") (pinfunction "GND_PAD") (pintype "bidirectional"))
      (node (ref "LDO_4") (pin "4") (pinfunction "GND_4") (pintype "bidirectional"))
      (node (ref "LDO_4") (pin "P1") (pinfunction "GND_P1") (pintype "bidirectional"))
      (node (ref "LDO_4") (pin "P2") (pinfunction "GND_P2") (pintype "bidirectional"))
      (node (ref "LDO_4") (pin "P3") (pinfunction "GND_P3") (pintype "bidirectional"))
      (node (ref "LDO_4") (pin "P4") (pinfunction "GND_P4") (pintype "bidirectional"))
      (node (ref "LDO_4") (pin "P5") (pinfunction "GND_P5") (pintype "bidirectional"))
      (node (ref "LDO_4") (pin "PAD") (pinfunction "GND_PAD") (pintype "bidirectional"))
      (node (ref "LDO_5") (pin "4") (pinfunction "GND_4") (pintype "bidirectional"))
      (node (ref "LDO_5") (pin "P1") (pinfunction "GND_P1") (pintype "bidirectional"))
      (node (ref "LDO_5") (pin "P2") (pinfunction "GND_P2") (pintype "bidirectional"))
      (node (ref "LDO_5") (pin "P3") (pinfunction "GND_P3") (pintype "bidirectional"))
      (node (ref "LDO_5") (pin "P4") (pinfunction "GND_P4") (pintype "bidirectional"))
      (node (ref "LDO_5") (pin "P5") (pinfunction "GND_P5") (pintype "bidirectional"))
      (node (ref "LDO_5") (pin "PAD") (pinfunction "GND_PAD") (pintype "bidirectional"))
      (node (ref "LDO_6") (pin "4") (pinfunction "GND_4") (pintype "bidirectional"))
      (node (ref "LDO_6") (pin "P1") (pinfunction "GND_P1") (pintype "bidirectional"))
      (node (ref "LDO_6") (pin "P2") (pinfunction "GND_P2") (pintype "bidirectional"))
      (node (ref "LDO_6") (pin "P3") (pinfunction "GND_P3") (pintype "bidirectional"))
      (node (ref "LDO_6") (pin "P4") (pinfunction "GND_P4") (pintype "bidirectional"))
      (node (ref "LDO_6") (pin "P5") (pinfunction "GND_P5") (pintype "bidirectional"))
      (node (ref "LDO_6") (pin "PAD") (pinfunction "GND_PAD") (pintype "bidirectional"))
      (node (ref "LDO_7") (pin "4") (pinfunction "GND_4") (pintype "bidirectional"))
      (node (ref "LDO_7") (pin "P1") (pinfunction "GND_P1") (pintype "bidirectional"))
      (node (ref "LDO_7") (pin "P2") (pinfunction "GND_P2") (pintype "bidirectional"))
      (node (ref "LDO_7") (pin "P3") (pinfunction "GND_P3") (pintype "bidirectional"))
      (node (ref "LDO_7") (pin "P4") (pinfunction "GND_P4") (pintype "bidirectional"))
      (node (ref "LDO_7") (pin "P5") (pinfunction "GND_P5") (pintype "bidirectional"))
      (node (ref "LDO_7") (pin "PAD") (pinfunction "GND_PAD") (pintype "bidirectional"))
      (node (ref "LDO_8") (pin "4") (pinfunction "GND_4") (pintype "bidirectional"))
      (node (ref "LDO_8") (pin "P1") (pinfunction "GND_P1") (pintype "bidirectional"))
      (node (ref "LDO_8") (pin "P2") (pinfunction "GND_P2") (pintype "bidirectional"))
      (node (ref "LDO_8") (pin "P3") (pinfunction "GND_P3") (pintype "bidirectional"))
      (node (ref "LDO_8") (pin "P4") (pinfunction "GND_P4") (pintype "bidirectional"))
      (node (ref "LDO_8") (pin "P5") (pinfunction "GND_P5") (pintype "bidirectional"))
      (node (ref "LDO_8") (pin "PAD") (pinfunction "GND_PAD") (pintype "bidirectional"))
      (node (ref "LDO_9") (pin "4") (pinfunction "GND_4") (pintype "bidirectional"))
      (node (ref "LDO_9") (pin "P1") (pinfunction "GND_P1") (pintype "bidirectional"))
      (node (ref "LDO_9") (pin "P2") (pinfunction "GND_P2") (pintype "bidirectional"))
      (node (ref "LDO_9") (pin "P3") (pinfunction "GND_P3") (pintype "bidirectional"))
      (node (ref "LDO_9") (pin "P4") (pinfunction "GND_P4") (pintype "bidirectional"))
      (node (ref "LDO_9") (pin "P5") (pinfunction "GND_P5") (pintype "bidirectional"))
      (node (ref "LDO_9") (pin "PAD") (pinfunction "GND_PAD") (pintype "bidirectional"))
      (node (ref "LED1") (pin "C") (pinfunction "C_C") (pintype "passive"))
      (node (ref "LNA_1") (pin "2") (pinfunction "GND_2") (pintype "bidirectional"))
      (node (ref "LNA_1") (pin "4") (pinfunction "GND_1_4") (pintype "bidirectional"))
      (node (ref "LNA_10") (pin "2") (pinfunction "GND_2") (pintype "bidirectional"))
      (node (ref "LNA_10") (pin "4") (pinfunction "GND_1_4") (pintype "bidirectional"))
      (node (ref "LNA_11") (pin "2") (pinfunction "GND_2") (pintype "bidirectional"))
      (node (ref "LNA_11") (pin "4") (pinfunction "GND_1_4") (pintype "bidirectional"))
      (node (ref "LNA_12") (pin "2") (pinfunction "GND_2") (pintype "bidirectional"))
      (node (ref "LNA_12") (pin "4") (pinfunction "GND_1_4") (pintype "bidirectional"))
      (node (ref "LNA_2") (pin "2") (pinfunction "GND_2") (pintype "bidirectional"))
      (node (ref "LNA_2") (pin "4") (pinfunction "GND_1_4") (pintype "bidirectional"))
      (node (ref "LNA_3") (pin "2") (pinfunction "GND_2") (pintype "bidirectional"))
      (node (ref "LNA_3") (pin "4") (pinfunction "GND_1_4") (pintype "bidirectional"))
      (node (ref "LNA_4") (pin "2") (pinfunction "GND_2") (pintype "bidirectional"))
      (node (ref "LNA_4") (pin "4") (pinfunction "GND_1_4") (pintype "bidirectional"))
      (node (ref "LNA_5") (pin "2") (pinfunction "GND_2") (pintype "bidirectional"))
      (node (ref "LNA_5") (pin "4") (pinfunction "GND_1_4") (pintype "bidirectional"))
      (node (ref "LNA_6") (pin "2") (pinfunction "GND_2") (pintype "bidirectional"))
      (node (ref "LNA_6") (pin "4") (pinfunction "GND_1_4") (pintype "bidirectional"))
      (node (ref "LNA_7") (pin "2") (pinfunction "GND_2") (pintype "bidirectional"))
      (node (ref "LNA_7") (pin "4") (pinfunction "GND_1_4") (pintype "bidirectional"))
      (node (ref "LNA_8") (pin "2") (pinfunction "GND_2") (pintype "bidirectional"))
      (node (ref "LNA_8") (pin "4") (pinfunction "GND_1_4") (pintype "bidirectional"))
      (node (ref "LNA_9") (pin "2") (pinfunction "GND_2") (pintype "bidirectional"))
      (node (ref "LNA_9") (pin "4") (pinfunction "GND_1_4") (pintype "bidirectional"))
      (node (ref "Q2") (pin "2") (pinfunction "S_2") (pintype "passive"))
      (node (ref "R10") (pin "2") (pinfunction "2_2") (pintype "passive"))
      (node (ref "R13") (pin "2") (pinfunction "2_2") (pintype "passive"))
      (node (ref "R14") (pin "2") (pinfunction "2_2") (pintype "passive"))
      (node (ref "R19") (pin "2") (pinfunction "2_2") (pintype "passive"))
      (node (ref "R205") (pin "1") (pinfunction "1_1") (pintype "passive"))
      (node (ref "R206") (pin "1") (pinfunction "1_1") (pintype "passive"))
      (node (ref "R23") (pin "2") (pinfunction "2_2") (pintype "passive"))
      (node (ref "R26") (pin "2") (pinfunction "2_2") (pintype "passive"))
      (node (ref "R29") (pin "2") (pinfunction "2_2") (pintype "passive"))
      (node (ref "R3") (pin "2") (pinfunction "2_2") (pintype "passive"))
      (node (ref "R32") (pin "2") (pinfunction "2_2") (pintype "passive"))
      (node (ref "R35") (pin "2") (pinfunction "2_2") (pintype "passive"))
      (node (ref "R38") (pin "2") (pinfunction "2_2") (pintype "passive"))
      (node (ref "R41") (pin "2") (pinfunction "2_2") (pintype "passive"))
      (node (ref "R7") (pin "2") (pinfunction "2_2") (pintype "passive"))
      (node (ref "SAW_1") (pin "2") (pinfunction "GND_1_2") (pintype "bidirectional"))
      (node (ref "SAW_1") (pin "3") (pinfunction "GND_2_3") (pintype "bidirectional"))
      (node (ref "SAW_1") (pin "4") (pinfunction "GND_3_4") (pintype "bidirectional"))
      (node (ref "SAW_1") (pin "5") (pinfunction "GND_4_5") (pintype "bidirectional"))
      (node (ref "SAW_1") (pin "6") (pinfunction "GND_5_6") (pintype "bidirectional"))
      (node (ref "SAW_1") (pin "7") (pinfunction "GND_6_7") (pintype "bidirectional"))
      (node (ref "SAW_10") (pin "1") (pinfunction "GND_1") (pintype "bidirectional"))
      (node (ref "SAW_10") (pin "3") (pinfunction "GND_1_3") (pintype "bidirectional"))
      (node (ref "SAW_10") (pin "4") (pinfunction "GND_2_4") (pintype "bidirectional"))
      (node (ref "SAW_10") (pin "6") (pinfunction "GND_3_6") (pintype "bidirectional"))
      (node (ref "SAW_11") (pin "1") (pinfunction "GND_1") (pintype "bidirectional"))
      (node (ref "SAW_11") (pin "3") (pinfunction "GND_1_3") (pintype "bidirectional"))
      (node (ref "SAW_11") (pin "4") (pinfunction "GND_2_4") (pintype "bidirectional"))
      (node (ref "SAW_11") (pin "6") (pinfunction "GND_3_6") (pintype "bidirectional"))
      (node (ref "SAW_12") (pin "1") (pinfunction "GND_1") (pintype "bidirectional"))
      (node (ref "SAW_12") (pin "3") (pinfunction "GND_1_3") (pintype "bidirectional"))
      (node (ref "SAW_12") (pin "4") (pinfunction "GND_2_4") (pintype "bidirectional"))
      (node (ref "SAW_12") (pin "6") (pinfunction "GND_3_6") (pintype "bidirectional"))
      (node (ref "SAW_13") (pin "1") (pinfunction "INPUT_GROUND_1") (pintype "bidirectional"))
      (node (ref "SAW_13") (pin "2") (pinfunction "GROUND_1_2") (pintype "bidirectional"))
      (node (ref "SAW_13") (pin "3") (pinfunction "GROUND_2_3") (pintype "bidirectional"))
      (node (ref "SAW_13") (pin "4") (pinfunction "GROUND_3_4") (pintype "bidirectional"))
      (node (ref "SAW_13") (pin "6") (pinfunction "OUTPUT_GROUND_6") (pintype "bidirectional"))
      (node (ref "SAW_13") (pin "7") (pinfunction "GROUND_4_7") (pintype "bidirectional"))
      (node (ref "SAW_13") (pin "8") (pinfunction "GROUND_5_8") (pintype "bidirectional"))
      (node (ref "SAW_13") (pin "9") (pinfunction "GROUND_6_9") (pintype "bidirectional"))
      (node (ref "SAW_14") (pin "1") (pinfunction "INPUT_GROUND_1") (pintype "bidirectional"))
      (node (ref "SAW_14") (pin "2") (pinfunction "GROUND_1_2") (pintype "bidirectional"))
      (node (ref "SAW_14") (pin "3") (pinfunction "GROUND_2_3") (pintype "bidirectional"))
      (node (ref "SAW_14") (pin "4") (pinfunction "GROUND_3_4") (pintype "bidirectional"))
      (node (ref "SAW_14") (pin "6") (pinfunction "OUTPUT_GROUND_6") (pintype "bidirectional"))
      (node (ref "SAW_14") (pin "7") (pinfunction "GROUND_4_7") (pintype "bidirectional"))
      (node (ref "SAW_14") (pin "8") (pinfunction "GROUND_5_8") (pintype "bidirectional"))
      (node (ref "SAW_14") (pin "9") (pinfunction "GROUND_6_9") (pintype "bidirectional"))
      (node (ref "SAW_15") (pin "1") (pinfunction "INPUT_GROUND_1") (pintype "bidirectional"))
      (node (ref "SAW_15") (pin "2") (pinfunction "GROUND_1_2") (pintype "bidirectional"))
      (node (ref "SAW_15") (pin "3") (pinfunction "GROUND_2_3") (pintype "bidirectional"))
      (node (ref "SAW_15") (pin "4") (pinfunction "GROUND_3_4") (pintype "bidirectional"))
      (node (ref "SAW_15") (pin "6") (pinfunction "OUTPUT_GROUND_6") (pintype "bidirectional"))
      (node (ref "SAW_15") (pin "7") (pinfunction "GROUND_4_7") (pintype "bidirectional"))
      (node (ref "SAW_15") (pin "8") (pinfunction "GROUND_5_8") (pintype "bidirectional"))
      (node (ref "SAW_15") (pin "9") (pinfunction "GROUND_6_9") (pintype "bidirectional"))
      (node (ref "SAW_16") (pin "1") (pinfunction "INPUT_GROUND_1") (pintype "bidirectional"))
      (node (ref "SAW_16") (pin "2") (pinfunction "GROUND_1_2") (pintype "bidirectional"))
      (node (ref "SAW_16") (pin "3") (pinfunction "GROUND_2_3") (pintype "bidirectional"))
      (node (ref "SAW_16") (pin "4") (pinfunction "GROUND_3_4") (pintype "bidirectional"))
      (node (ref "SAW_16") (pin "6") (pinfunction "OUTPUT_GROUND_6") (pintype "bidirectional"))
      (node (ref "SAW_16") (pin "7") (pinfunction "GROUND_4_7") (pintype "bidirectional"))
      (node (ref "SAW_16") (pin "8") (pinfunction "GROUND_5_8") (pintype "bidirectional"))
      (node (ref "SAW_16") (pin "9") (pinfunction "GROUND_6_9") (pintype "bidirectional"))
      (node (ref "SAW_2") (pin "1") (pinfunction "GND_1") (pintype "bidirectional"))
      (node (ref "SAW_2") (pin "3") (pinfunction "GND_1_3") (pintype "bidirectional"))
      (node (ref "SAW_2") (pin "4") (pinfunction "CASE_GND_4") (pintype "bidirectional"))
      (node (ref "SAW_2") (pin "5") (pinfunction "GND_2_5") (pintype "bidirectional"))
      (node (ref "SAW_2") (pin "7") (pinfunction "GND_3_7") (pintype "bidirectional"))
      (node (ref "SAW_2") (pin "8") (pinfunction "CASE_GND_1_8") (pintype "bidirectional"))
      (node (ref "SAW_3") (pin "1") (pinfunction "GND_1") (pintype "bidirectional"))
      (node (ref "SAW_3") (pin "3") (pinfunction "GND_1_3") (pintype "bidirectional"))
      (node (ref "SAW_3") (pin "4") (pinfunction "CASE_GND_4") (pintype "bidirectional"))
      (node (ref "SAW_3") (pin "5") (pinfunction "GND_2_5") (pintype "bidirectional"))
      (node (ref "SAW_3") (pin "7") (pinfunction "GND_3_7") (pintype "bidirectional"))
      (node (ref "SAW_3") (pin "8") (pinfunction "CASE_GND_1_8") (pintype "bidirectional"))
      (node (ref "SAW_4") (pin "1") (pinfunction "GND_1") (pintype "bidirectional"))
      (node (ref "SAW_4") (pin "3") (pinfunction "GND_1_3") (pintype "bidirectional"))
      (node (ref "SAW_4") (pin "4") (pinfunction "CASE_GND_4") (pintype "bidirectional"))
      (node (ref "SAW_4") (pin "5") (pinfunction "GND_2_5") (pintype "bidirectional"))
      (node (ref "SAW_4") (pin "7") (pinfunction "GND_3_7") (pintype "bidirectional"))
      (node (ref "SAW_4") (pin "8") (pinfunction "CASE_GND_1_8") (pintype "bidirectional"))
      (node (ref "SAW_5") (pin "1") (pinfunction "GND_1") (pintype "bidirectional"))
      (node (ref "SAW_5") (pin "3") (pinfunction "GND_1_3") (pintype "bidirectional"))
      (node (ref "SAW_5") (pin "4") (pinfunction "CASE_GND_4") (pintype "bidirectional"))
      (node (ref "SAW_5") (pin "5") (pinfunction "GND_2_5") (pintype "bidirectional"))
      (node (ref "SAW_5") (pin "7") (pinfunction "GND_3_7") (pintype "bidirectional"))
      (node (ref "SAW_5") (pin "8") (pinfunction "CASE_GND_1_8") (pintype "bidirectional"))
      (node (ref "SAW_6") (pin "1") (pinfunction "GND_1") (pintype "bidirectional"))
      (node (ref "SAW_6") (pin "3") (pinfunction "GND_1_3") (pintype "bidirectional"))
      (node (ref "SAW_6") (pin "4") (pinfunction "CASE_GND_4") (pintype "bidirectional"))
      (node (ref "SAW_6") (pin "5") (pinfunction "GND_2_5") (pintype "bidirectional"))
      (node (ref "SAW_6") (pin "7") (pinfunction "GND_3_7") (pintype "bidirectional"))
      (node (ref "SAW_6") (pin "8") (pinfunction "CASE_GND_1_8") (pintype "bidirectional"))
      (node (ref "SAW_7") (pin "1") (pinfunction "GND_1") (pintype "bidirectional"))
      (node (ref "SAW_7") (pin "3") (pinfunction "GND_1_3") (pintype "bidirectional"))
      (node (ref "SAW_7") (pin "4") (pinfunction "CASE_GND_4") (pintype "bidirectional"))
      (node (ref "SAW_7") (pin "5") (pinfunction "GND_2_5") (pintype "bidirectional"))
      (node (ref "SAW_7") (pin "7") (pinfunction "GND_3_7") (pintype "bidirectional"))
      (node (ref "SAW_7") (pin "8") (pinfunction "CASE_GND_1_8") (pintype "bidirectional"))
      (node (ref "SAW_8") (pin "1") (pinfunction "GND_1") (pintype "bidirectional"))
      (node (ref "SAW_8") (pin "3") (pinfunction "GND_1_3") (pintype "bidirectional"))
      (node (ref "SAW_8") (pin "4") (pinfunction "CASE_GND_4") (pintype "bidirectional"))
      (node (ref "SAW_8") (pin "5") (pinfunction "GND_2_5") (pintype "bidirectional"))
      (node (ref "SAW_8") (pin "7") (pinfunction "GND_3_7") (pintype "bidirectional"))
      (node (ref "SAW_8") (pin "8") (pinfunction "CASE_GND_1_8") (pintype "bidirectional"))
      (node (ref "SAW_9") (pin "1") (pinfunction "GND_1") (pintype "bidirectional"))
      (node (ref "SAW_9") (pin "3") (pinfunction "GND_1_3") (pintype "bidirectional"))
      (node (ref "SAW_9") (pin "4") (pinfunction "GND_2_4") (pintype "bidirectional"))
      (node (ref "SAW_9") (pin "6") (pinfunction "GND_3_6") (pintype "bidirectional"))
      (node (ref "X1") (pin "2") (pinfunction "GND_2") (pintype "power_in"))
      (node (ref "X10") (pin "2") (pinfunction "GND_2") (pintype "power_in"))
      (node (ref "X11") (pin "2") (pinfunction "GND_2") (pintype "power_in"))
      (node (ref "X12") (pin "2") (pinfunction "GND_2") (pintype "power_in"))
      (node (ref "X13") (pin "2") (pinfunction "GND_2") (pintype "power_in"))
      (node (ref "X14") (pin "2") (pinfunction "GND_2") (pintype "power_in"))
      (node (ref "X15") (pin "2") (pinfunction "GND_2") (pintype "power_in"))
      (node (ref "X16") (pin "2") (pinfunction "GND_2") (pintype "power_in"))
      (node (ref "X17") (pin "2") (pinfunction "GND_2") (pintype "power_in"))
      (node (ref "X18") (pin "2") (pinfunction "GND_2") (pintype "power_in"))
      (node (ref "X19") (pin "2") (pinfunction "GND_2") (pintype "power_in"))
      (node (ref "X2") (pin "2") (pinfunction "GND_2") (pintype "power_in"))
      (node (ref "X20") (pin "2") (pinfunction "GND_2") (pintype "power_in"))
      (node (ref "X21") (pin "2") (pinfunction "GND_2") (pintype "power_in"))
      (node (ref "X22") (pin "2") (pinfunction "GND_2") (pintype "power_in"))
      (node (ref "X23") (pin "2") (pinfunction "GND_2") (pintype "power_in"))
      (node (ref "X24") (pin "2") (pinfunction "GND_2") (pintype "power_in"))
      (node (ref "X25") (pin "2") (pinfunction "GND_2") (pintype "power_in"))
      (node (ref "X26") (pin "2") (pinfunction "GND_2") (pintype "power_in"))
      (node (ref "X27") (pin "2") (pinfunction "GND_2") (pintype "power_in"))
      (node (ref "X28") (pin "2") (pinfunction "GND_2") (pintype "power_in"))
      (node (ref "X29") (pin "2") (pinfunction "GND_2") (pintype "power_in"))
      (node (ref "X3") (pin "2") (pinfunction "GND_2") (pintype "power_in"))
      (node (ref "X30") (pin "2") (pinfunction "GND_2") (pintype "power_in"))
      (node (ref "X31") (pin "2") (pinfunction "GND_2") (pintype "power_in"))
      (node (ref "X32") (pin "2") (pinfunction "GND_2") (pintype "power_in"))
      (node (ref "X4") (pin "2") (pinfunction "GND_2") (pintype "power_in"))
      (node (ref "X5") (pin "2") (pinfunction "GND_2") (pintype "power_in"))
      (node (ref "X6") (pin "2") (pinfunction "GND_2") (pintype "power_in"))
      (node (ref "X7") (pin "2") (pinfunction "GND_2") (pintype "power_in"))
      (node (ref "X8") (pin "2") (pinfunction "GND_2") (pintype "power_in"))
      (node (ref "X9") (pin "2") (pinfunction "GND_2") (pintype "power_in"))
    )
    (net (code "5") (name "Net-(C2-Pad1)") (class "Default")
      (node (ref "C2") (pin "1") (pinfunction "1_1") (pintype "passive"))
      (node (ref "C3") (pin "1") (pinfunction "1_1") (pintype "passive"))
      (node (ref "C54") (pin "2") (pinfunction "2_2") (pintype "passive"))
      (node (ref "C56") (pin "OUT") (pinfunction "OUT_OUT") (pintype "bidirectional"))
      (node (ref "L1") (pin "2") (pinfunction "2_2") (pintype "passive"))
      (node (ref "R2") (pin "1") (pinfunction "1_1") (pintype "passive"))
      (node (ref "TP_1") (pin "TP") (pinfunction "TP_TP") (pintype "input"))
    )
    (net (code "6") (name "Net-(C10-Pad1)") (class "Default")
      (node (ref "C10") (pin "1") (pinfunction "1_1") (pintype "passive"))
      (node (ref "C11") (pin "1") (pinfunction "1_1") (pintype "passive"))
      (node (ref "C63") (pin "2") (pinfunction "2_2") (pintype "passive"))
      (node (ref "C65") (pin "OUT") (pinfunction "OUT_OUT") (pintype "bidirectional"))
      (node (ref "L7") (pin "1") (pinfunction "1_1") (pintype "passive"))
      (node (ref "R9") (pin "1") (pinfunction "1_1") (pintype "passive"))
      (node (ref "TP_3") (pin "TP") (pinfunction "TP_TP") (pintype "input"))
    )
    (net (code "7") (name "Net-(C13-Pad2)") (class "Default")
      (node (ref "C13") (pin "2") (pinfunction "2_2") (pintype "passive"))
      (node (ref "X8") (pin "1") (pinfunction "1_1") (pintype "passive"))
    )
    (net (code "8") (name "Net-(C14-Pad1)") (class "Default")
      (node (ref "C14") (pin "1") (pinfunction "1_1") (pintype "passive"))
      (node (ref "X9") (pin "1") (pinfunction "1_1") (pintype "passive"))
    )
    (net (code "9") (name "Net-(C15-Pad1)") (class "Default")
      (node (ref "C15") (pin "1") (pinfunction "1_1") (pintype "passive"))
      (node (ref "C16") (pin "1") (pinfunction "1_1") (pintype "passive"))
      (node (ref "C67") (pin "2") (pinfunction "2_2") (pintype "passive"))
      (node (ref "C69") (pin "OUT") (pinfunction "OUT_OUT") (pintype "bidirectional"))
      (node (ref "L10") (pin "2") (pinfunction "2_2") (pintype "passive"))
      (node (ref "R12") (pin "1") (pinfunction "1_1") (pintype "passive"))
      (node (ref "TP_4") (pin "TP") (pinfunction "TP_TP") (pintype "input"))
    )
    (net (code "10") (name "Net-(C19-Pad1)") (class "Default")
      (node (ref "C19") (pin "1") (pinfunction "1_1") (pintype "passive"))
      (node (ref "C20") (pin "1") (pinfunction "1_1") (pintype "passive"))
      (node (ref "C71") (pin "2") (pinfunction "2_2") (pintype "passive"))
      (node (ref "C75") (pin "OUT") (pinfunction "OUT_OUT") (pintype "bidirectional"))
      (node (ref "L11") (pin "2") (pinfunction "2_2") (pintype "passive"))
      (node (ref "R16") (pin "1") (pinfunction "1_1") (pintype "passive"))
      (node (ref "TP_5") (pin "TP") (pinfunction "TP_TP") (pintype "input"))
    )
    (net (code "11") (name "Net-(C23-Pad1)") (class "Default")
      (node (ref "C23") (pin "1") (pinfunction "1_1") (pintype "passive"))
      (node (ref "C24") (pin "1") (pinfunction "1_1") (pintype "passive"))
      (node (ref "C77") (pin "2") (pinfunction "2_2") (pintype "passive"))
      (node (ref "C79") (pin "OUT") (pinfunction "OUT_OUT") (pintype "bidirectional"))
      (node (ref "L12") (pin "1") (pinfunction "1_1") (pintype "passive"))
      (node (ref "R22") (pin "1") (pinfunction "1_1") (pintype "passive"))
      (node (ref "TP_6") (pin "TP") (pinfunction "TP_TP") (pintype "input"))
    )
    (net (code "12") (name "Net-(C26-Pad1)") (class "Default")
      (node (ref "C26") (pin "1") (pinfunction "1_1") (pintype "passive"))
      (node (ref "X17") (pin "1") (pinfunction "1_1") (pintype "passive"))
    )
    (net (code "13") (name "Net-(C27-Pad1)") (class "Default")
      (node (ref "C27") (pin "1") (pinfunction "1_1") (pintype "passive"))
      (node (ref "C28") (pin "1") (pinfunction "1_1") (pintype "passive"))
      (node (ref "C81") (pin "2") (pinfunction "2_2") (pintype "passive"))
      (node (ref "C83") (pin "OUT") (pinfunction "OUT_OUT") (pintype "bidirectional"))
      (node (ref "L13") (pin "2") (pinfunction "2_2") (pintype "passive"))
      (node (ref "R25") (pin "1") (pinfunction "1_1") (pintype "passive"))
      (node (ref "TP_7") (pin "TP") (pinfunction "TP_TP") (pintype "input"))
    )
    (net (code "14") (name "Net-(C31-Pad1)") (class "Default")
      (node (ref "C31") (pin "1") (pinfunction "1_1") (pintype "passive"))
      (node (ref "C32") (pin "1") (pinfunction "1_1") (pintype "passive"))
      (node (ref "C85") (pin "2") (pinfunction "2_2") (pintype "passive"))
      (node (ref "C87") (pin "OUT") (pinfunction "OUT_OUT") (pintype "bidirectional"))
      (node (ref "L14") (pin "2") (pinfunction "2_2") (pintype "passive"))
      (node (ref "R28") (pin "1") (pinfunction "1_1") (pintype "passive"))
      (node (ref "TP_8") (pin "TP") (pinfunction "TP_TP") (pintype "input"))
    )
    (net (code "15") (name "Net-(C35-Pad1)") (class "Default")
      (node (ref "C35") (pin "1") (pinfunction "1_1") (pintype "passive"))
      (node (ref "C36") (pin "1") (pinfunction "1_1") (pintype "passive"))
      (node (ref "C89") (pin "2") (pinfunction "2_2") (pintype "passive"))
      (node (ref "C91") (pin "OUT") (pinfunction "OUT_OUT") (pintype "bidirectional"))
      (node (ref "L15") (pin "2") (pinfunction "2_2") (pintype "passive"))
      (node (ref "R31") (pin "1") (pinfunction "1_1") (pintype "passive"))
      (node (ref "TP_9") (pin "TP") (pinfunction "TP_TP") (pintype "input"))
    )
    (net (code "16") (name "Net-(C38-Pad1)") (class "Default")
      (node (ref "C38") (pin "1") (pinfunction "1_1") (pintype "passive"))
      (node (ref "L16") (pin "1") (pinfunction "1_1") (pintype "passive"))
      (node (ref "X25") (pin "1") (pinfunction "1_1") (pintype "passive"))
    )
    (net (code "17") (name "Net-(C40-Pad1)") (class "Default")
      (node (ref "C40") (pin "1") (pinfunction "1_1") (pintype "passive"))
      (node (ref "C41") (pin "1") (pinfunction "1_1") (pintype "passive"))
      (node (ref "C93") (pin "2") (pinfunction "2_2") (pintype "passive"))
      (node (ref "C95") (pin "OUT") (pinfunction "OUT_OUT") (pintype "bidirectional"))
      (node (ref "L18") (pin "2") (pinfunction "2_2") (pintype "passive"))
      (node (ref "R34") (pin "1") (pinfunction "1_1") (pintype "passive"))
      (node (ref "TP_10") (pin "TP") (pinfunction "TP_TP") (pintype "input"))
    )
    (net (code "18") (name "Net-(C44-Pad1)") (class "Default")
      (node (ref "C44") (pin "1") (pinfunction "1_1") (pintype "passive"))
      (node (ref "C45") (pin "1") (pinfunction "1_1") (pintype "passive"))
      (node (ref "C97") (pin "2") (pinfunction "2_2") (pintype "passive"))
      (node (ref "C99") (pin "OUT") (pinfunction "OUT_OUT") (pintype "bidirectional"))
      (node (ref "L21") (pin "2") (pinfunction "2_2") (pintype "passive"))
      (node (ref "R37") (pin "1") (pinfunction "1_1") (pintype "passive"))
      (node (ref "TP_11") (pin "TP") (pinfunction "TP_TP") (pintype "input"))
    )
    (net (code "19") (name "Net-(C51-Pad2)") (class "Default")
      (node (ref "C51") (pin "2") (pinfunction "2_2") (pintype "passive"))
      (node (ref "L26") (pin "1") (pinfunction "1_1") (pintype "passive"))
      (node (ref "X32") (pin "1") (pinfunction "1_1") (pintype "passive"))
    )
    (net (code "20") (name "Net-(C55-PadOUT)") (class "Default")
      (node (ref "C55") (pin "OUT") (pinfunction "OUT_OUT") (pintype "bidirectional"))
      (node (ref "LDO_1") (pin "7") (pinfunction "IN_7") (pintype "bidirectional"))
      (node (ref "LDO_1") (pin "8") (pinfunction "IN_8") (pintype "bidirectional"))
    )
    (net (code "21") (name "Net-(C56-PadIN)") (class "Default")
      (node (ref "C56") (pin "IN") (pinfunction "IN_IN") (pintype "bidirectional"))
      (node (ref "LDO_1") (pin "1") (pinfunction "OUT_1") (pintype "bidirectional"))
      (node (ref "LDO_1") (pin "2") (pinfunction "OUT_2") (pintype "bidirectional"))
    )
    (net (code "22") (name "Net-(C59-Pad2)") (class "Default")
      (node (ref "C59") (pin "2") (pinfunction "2_2") (pintype "passive"))
      (node (ref "C6") (pin "1") (pinfunction "1_1") (pintype "passive"))
      (node (ref "C61") (pin "OUT") (pinfunction "OUT_OUT") (pintype "bidirectional"))
      (node (ref "C7") (pin "1") (pinfunction "1_1") (pintype "passive"))
      (node (ref "L4") (pin "2") (pinfunction "2_2") (pintype "passive"))
      (node (ref "R6") (pin "1") (pinfunction "1_1") (pintype "passive"))
      (node (ref "TP_2") (pin "TP") (pinfunction "TP_TP") (pintype "input"))
    )
    (net (code "23") (name "Net-(C60-PadOUT)") (class "Default")
      (node (ref "C60") (pin "OUT") (pinfunction "OUT_OUT") (pintype "bidirectional"))
      (node (ref "LDO_2") (pin "7") (pinfunction "IN_7") (pintype "bidirectional"))
      (node (ref "LDO_2") (pin "8") (pinfunction "IN_8") (pintype "bidirectional"))
    )
    (net (code "24") (name "Net-(C61-PadIN)") (class "Default")
      (node (ref "C61") (pin "IN") (pinfunction "IN_IN") (pintype "bidirectional"))
      (node (ref "LDO_2") (pin "1") (pinfunction "OUT_1") (pintype "bidirectional"))
      (node (ref "LDO_2") (pin "2") (pinfunction "OUT_2") (pintype "bidirectional"))
    )
    (net (code "25") (name "Net-(C64-PadOUT)") (class "Default")
      (node (ref "C64") (pin "OUT") (pinfunction "OUT_OUT") (pintype "bidirectional"))
      (node (ref "LDO_3") (pin "7") (pinfunction "IN_7") (pintype "bidirectional"))
      (node (ref "LDO_3") (pin "8") (pinfunction "IN_8") (pintype "bidirectional"))
    )
    (net (code "26") (name "Net-(C65-PadIN)") (class "Default")
      (node (ref "C65") (pin "IN") (pinfunction "IN_IN") (pintype "bidirectional"))
      (node (ref "LDO_3") (pin "1") (pinfunction "OUT_1") (pintype "bidirectional"))
      (node (ref "LDO_3") (pin "2") (pinfunction "OUT_2") (pintype "bidirectional"))
    )
    (net (code "27") (name "Net-(C68-PadOUT)") (class "Default")
      (node (ref "C68") (pin "OUT") (pinfunction "OUT_OUT") (pintype "bidirectional"))
      (node (ref "LDO_4") (pin "7") (pinfunction "IN_7") (pintype "bidirectional"))
      (node (ref "LDO_4") (pin "8") (pinfunction "IN_8") (pintype "bidirectional"))
    )
    (net (code "28") (name "Net-(C69-PadIN)") (class "Default")
      (node (ref "C69") (pin "IN") (pinfunction "IN_IN") (pintype "bidirectional"))
      (node (ref "LDO_4") (pin "1") (pinfunction "OUT_1") (pintype "bidirectional"))
      (node (ref "LDO_4") (pin "2") (pinfunction "OUT_2") (pintype "bidirectional"))
    )
    (net (code "29") (name "Net-(C74-PadOUT)") (class "Default")
      (node (ref "C74") (pin "OUT") (pinfunction "OUT_OUT") (pintype "bidirectional"))
      (node (ref "LDO_5") (pin "7") (pinfunction "IN_7") (pintype "bidirectional"))
      (node (ref "LDO_5") (pin "8") (pinfunction "IN_8") (pintype "bidirectional"))
    )
    (net (code "30") (name "Net-(C75-PadIN)") (class "Default")
      (node (ref "C75") (pin "IN") (pinfunction "IN_IN") (pintype "bidirectional"))
      (node (ref "LDO_5") (pin "1") (pinfunction "OUT_1") (pintype "bidirectional"))
      (node (ref "LDO_5") (pin "2") (pinfunction "OUT_2") (pintype "bidirectional"))
    )
    (net (code "31") (name "Net-(C78-PadOUT)") (class "Default")
      (node (ref "C78") (pin "OUT") (pinfunction "OUT_OUT") (pintype "bidirectional"))
      (node (ref "LDO_6") (pin "7") (pinfunction "IN_7") (pintype "bidirectional"))
      (node (ref "LDO_6") (pin "8") (pinfunction "IN_8") (pintype "bidirectional"))
    )
    (net (code "32") (name "Net-(C79-PadIN)") (class "Default")
      (node (ref "C79") (pin "IN") (pinfunction "IN_IN") (pintype "bidirectional"))
      (node (ref "LDO_6") (pin "1") (pinfunction "OUT_1") (pintype "bidirectional"))
      (node (ref "LDO_6") (pin "2") (pinfunction "OUT_2") (pintype "bidirectional"))
    )
    (net (code "33") (name "Net-(C82-PadOUT)") (class "Default")
      (node (ref "C82") (pin "OUT") (pinfunction "OUT_OUT") (pintype "bidirectional"))
      (node (ref "LDO_7") (pin "7") (pinfunction "IN_7") (pintype "bidirectional"))
      (node (ref "LDO_7") (pin "8") (pinfunction "IN_8") (pintype "bidirectional"))
    )
    (net (code "34") (name "Net-(C83-PadIN)") (class "Default")
      (node (ref "C83") (pin "IN") (pinfunction "IN_IN") (pintype "bidirectional"))
      (node (ref "LDO_7") (pin "1") (pinfunction "OUT_1") (pintype "bidirectional"))
      (node (ref "LDO_7") (pin "2") (pinfunction "OUT_2") (pintype "bidirectional"))
    )
    (net (code "35") (name "Net-(C86-PadOUT)") (class "Default")
      (node (ref "C86") (pin "OUT") (pinfunction "OUT_OUT") (pintype "bidirectional"))
      (node (ref "LDO_8") (pin "7") (pinfunction "IN_7") (pintype "bidirectional"))
      (node (ref "LDO_8") (pin "8") (pinfunction "IN_8") (pintype "bidirectional"))
    )
    (net (code "36") (name "Net-(C87-PadIN)") (class "Default")
      (node (ref "C87") (pin "IN") (pinfunction "IN_IN") (pintype "bidirectional"))
      (node (ref "LDO_8") (pin "1") (pinfunction "OUT_1") (pintype "bidirectional"))
      (node (ref "LDO_8") (pin "2") (pinfunction "OUT_2") (pintype "bidirectional"))
    )
    (net (code "37") (name "Net-(C90-PadOUT)") (class "Default")
      (node (ref "C90") (pin "OUT") (pinfunction "OUT_OUT") (pintype "bidirectional"))
      (node (ref "LDO_9") (pin "7") (pinfunction "IN_7") (pintype "bidirectional"))
      (node (ref "LDO_9") (pin "8") (pinfunction "IN_8") (pintype "bidirectional"))
    )
    (net (code "38") (name "Net-(C91-PadIN)") (class "Default")
      (node (ref "C91") (pin "IN") (pinfunction "IN_IN") (pintype "bidirectional"))
      (node (ref "LDO_9") (pin "1") (pinfunction "OUT_1") (pintype "bidirectional"))
      (node (ref "LDO_9") (pin "2") (pinfunction "OUT_2") (pintype "bidirectional"))
    )
    (net (code "39") (name "Net-(C94-PadOUT)") (class "Default")
      (node (ref "C94") (pin "OUT") (pinfunction "OUT_OUT") (pintype "bidirectional"))
      (node (ref "LDO_10") (pin "7") (pinfunction "IN_7") (pintype "bidirectional"))
      (node (ref "LDO_10") (pin "8") (pinfunction "IN_8") (pintype "bidirectional"))
    )
    (net (code "40") (name "Net-(C95-PadIN)") (class "Default")
      (node (ref "C95") (pin "IN") (pinfunction "IN_IN") (pintype "bidirectional"))
      (node (ref "LDO_10") (pin "1") (pinfunction "OUT_1") (pintype "bidirectional"))
      (node (ref "LDO_10") (pin "2") (pinfunction "OUT_2") (pintype "bidirectional"))
    )
    (net (code "41") (name "Net-(C98-PadOUT)") (class "Default")
      (node (ref "C98") (pin "OUT") (pinfunction "OUT_OUT") (pintype "bidirectional"))
      (node (ref "LDO_11") (pin "7") (pinfunction "IN_7") (pintype "bidirectional"))
      (node (ref "LDO_11") (pin "8") (pinfunction "IN_8") (pintype "bidirectional"))
    )
    (net (code "42") (name "Net-(C99-PadIN)") (class "Default")
      (node (ref "C99") (pin "IN") (pinfunction "IN_IN") (pintype "bidirectional"))
      (node (ref "LDO_11") (pin "1") (pinfunction "OUT_1") (pintype "bidirectional"))
      (node (ref "LDO_11") (pin "2") (pinfunction "OUT_2") (pintype "bidirectional"))
    )
    (net (code "43") (name "Net-(C101-Pad2)") (class "Default")
      (node (ref "C101") (pin "2") (pinfunction "2_2") (pintype "passive"))
      (node (ref "C103") (pin "OUT") (pinfunction "OUT_OUT") (pintype "bidirectional"))
      (node (ref "C48") (pin "1") (pinfunction "1_1") (pintype "passive"))
      (node (ref "C49") (pin "1") (pinfunction "1_1") (pintype "passive"))
      (node (ref "L24") (pin "2") (pinfunction "2_2") (pintype "passive"))
      (node (ref "R40") (pin "1") (pinfunction "1_1") (pintype "passive"))
      (node (ref "TP_12") (pin "TP") (pinfunction "TP_TP") (pintype "input"))
    )
    (net (code "44") (name "Net-(C102-PadOUT)") (class "Default")
      (node (ref "C102") (pin "OUT") (pinfunction "OUT_OUT") (pintype "bidirectional"))
      (node (ref "LDO_12") (pin "7") (pinfunction "IN_7") (pintype "bidirectional"))
      (node (ref "LDO_12") (pin "8") (pinfunction "IN_8") (pintype "bidirectional"))
    )
    (net (code "45") (name "Net-(C103-PadIN)") (class "Default")
      (node (ref "C103") (pin "IN") (pinfunction "IN_IN") (pintype "bidirectional"))
      (node (ref "LDO_12") (pin "1") (pinfunction "OUT_1") (pintype "bidirectional"))
      (node (ref "LDO_12") (pin "2") (pinfunction "OUT_2") (pintype "bidirectional"))
    )
    (net (code "46") (name "Net-(C459-PadIN)") (class "Default")
      (node (ref "C459") (pin "IN") (pinfunction "IN_IN") (pintype "bidirectional"))
      (node (ref "IC58") (pin "34") (pinfunction "VOUT_34") (pintype "bidirectional"))
      (node (ref "IC58") (pin "35") (pinfunction "VOUT_35") (pintype "bidirectional"))
      (node (ref "IC58") (pin "36") (pinfunction "VOUT_36") (pintype "bidirectional"))
      (node (ref "IC58") (pin "37") (pinfunction "VOUT_37") (pintype "bidirectional"))
      (node (ref "IC58") (pin "38") (pinfunction "VOUT_38") (pintype "bidirectional"))
      (node (ref "IC58") (pin "41") (pinfunction "VOUT_41") (pintype "bidirectional"))
    )
    (net (code "47") (name "Net-(C500-IN)") (class "Default")
      (node (ref "C500") (pin "1") (pinfunction "IN_1") (pintype "passive"))
      (node (ref "L31") (pin "2") (pinfunction "2_2") (pintype "passive"))
    )
    (net (code "48") (name "Net-(C500-OUT)") (class "Default")
      (node (ref "C481") (pin "1") (pinfunction "1_1") (pintype "passive"))
      (node (ref "C482") (pin "1") (pinfunction "1_1") (pintype "passive"))
      (node (ref "C483") (pin "+") (pinfunction "+_+") (pintype "passive"))
      (node (ref "C484") (pin "+") (pinfunction "+_+") (pintype "passive"))
      (node (ref "C489") (pin "1") (pinfunction "1_1") (pintype "passive"))
      (node (ref "C490") (pin "1") (pinfunction "1_1") (pintype "passive"))
      (node (ref "C491") (pin "1") (pinfunction "1_1") (pintype "passive"))
      (node (ref "C492") (pin "1") (pinfunction "1_1") (pintype "passive"))
      (node (ref "C493") (pin "1") (pinfunction "1_1") (pintype "passive"))
      (node (ref "C500") (pin "2") (pinfunction "OUT_2") (pintype "passive"))
      (node (ref "IC58") (pin "1") (pinfunction "PVIN_1") (pintype "bidirectional"))
      (node (ref "IC58") (pin "11") (pinfunction "PVIN_11") (pintype "bidirectional"))
      (node (ref "IC58") (pin "12") (pinfunction "PVIN_12") (pintype "bidirectional"))
      (node (ref "IC58") (pin "3") (pinfunction "VIN_3") (pintype "bidirectional"))
      (node (ref "IC58") (pin "39") (pinfunction "PVIN_39") (pintype "bidirectional"))
      (node (ref "IC58") (pin "40") (pinfunction "PVIN_40") (pintype "bidirectional"))
    )
    (net (code "49") (name "Net-(IC58-INH{slash}UVLO)") (class "Default")
      (node (ref "IC58") (pin "30") (pinfunction "INH/UVLO_30") (pintype "bidirectional"))
      (node (ref "Q2") (pin "1") (pinfunction "D_1") (pintype "passive"))
    )
    (net (code "50") (name "Net-(IC58-PH-Pad10)") (class "Default")
      (node (ref "IC58") (pin "10") (pinfunction "PH_10") (pintype "bidirectional"))
      (node (ref "IC58") (pin "13") (pinfunction "PH_13") (pintype "bidirectional"))
      (node (ref "IC58") (pin "14") (pinfunction "PH_14") (pintype "bidirectional"))
      (node (ref "IC58") (pin "15") (pinfunction "PH_15") (pintype "bidirectional"))
      (node (ref "IC58") (pin "16") (pinfunction "PH_16") (pintype "bidirectional"))
      (node (ref "IC58") (pin "17") (pinfunction "PH_17") (pintype "bidirectional"))
      (node (ref "IC58") (pin "18") (pinfunction "PH_18") (pintype "bidirectional"))
      (node (ref "IC58") (pin "19") (pinfunction "PH_19") (pintype "bidirectional"))
      (node (ref "IC58") (pin "42") (pinfunction "PH_42") (pintype "bidirectional"))
      (node (ref "IC58") (pin "42A") (pinfunction "PH_42A") (pintype "bidirectional"))
      (node (ref "IC58") (pin "42B") (pinfunction "PH_42B") (pintype "bidirectional"))
      (node (ref "IC58") (pin "42C") (pinfunction "PH_42C") (pintype "bidirectional"))
      (node (ref "IC58") (pin "42D") (pinfunction "PH_42D") (pintype "bidirectional"))
      (node (ref "IC58") (pin "42E") (pinfunction "PH_42E") (pintype "bidirectional"))
      (node (ref "IC58") (pin "42F") (pinfunction "PH_42F") (pintype "bidirectional"))
      (node (ref "IC58") (pin "42G") (pinfunction "PH_42G") (pintype "bidirectional"))
      (node (ref "IC58") (pin "42H") (pinfunction "PH_42H") (pintype "bidirectional"))
      (node (ref "IC58") (pin "42J") (pinfunction "PH_42J") (pintype "bidirectional"))
      (node (ref "IC58") (pin "42K") (pinfunction "PH_42K") (pintype "bidirectional"))
      (node (ref "IC58") (pin "42L") (pinfunction "PH_42L") (pintype "bidirectional"))
      (node (ref "IC58") (pin "42M") (pinfunction "PH_42M") (pintype "bidirectional"))
      (node (ref "IC58") (pin "42N") (pinfunction "PH_42N") (pintype "bidirectional"))
      (node (ref "IC58") (pin "42P") (pinfunction "PH_42P") (pintype "bidirectional"))
    )
    (net (code "51") (name "Net-(IC58-PWRGD)") (class "Default")
      (node (ref "IC58") (pin "8") (pinfunction "PWRGD_8") (pintype "bidirectional"))
      (node (ref "R4") (pin "1") (pinfunction "1_1") (pintype "passive"))
      (node (ref "TP10") (pin "TP") (pinfunction "TP_TP") (pintype "input"))
    )
    (net (code "52") (name "Net-(IC58-RT_CLK)") (class "Default")
      (node (ref "IC58") (pin "22") (pinfunction "RT_CLK_22") (pintype "bidirectional"))
      (node (ref "R206") (pin "2") (pinfunction "2_2") (pintype "passive"))
    )
    (net (code "53") (name "Net-(IC58-VADJ)") (class "Default")
      (node (ref "IC58") (pin "26") (pinfunction "VADJ_26") (pintype "bidirectional"))
      (node (ref "R205") (pin "2") (pinfunction "2_2") (pintype "passive"))
    )
    (net (code "54") (name "Net-(LDO_1-FB{slash}SNS)") (class "Default")
      (node (ref "C54") (pin "1") (pinfunction "1_1") (pintype "passive"))
      (node (ref "LDO_1") (pin "3") (pinfunction "FB/SNS_3") (pintype "bidirectional"))
      (node (ref "R2") (pin "2") (pinfunction "2_2") (pintype "passive"))
      (node (ref "R3") (pin "1") (pinfunction "1_1") (pintype "passive"))
    )
    (net (code "55") (name "Net-(LDO_1-NR)") (class "Default")
      (node (ref "C53") (pin "1") (pinfunction "1_1") (pintype "passive"))
      (node (ref "LDO_1") (pin "6") (pinfunction "NR_6") (pintype "bidirectional"))
    )
    (net (code "56") (name "Net-(LDO_2-FB{slash}SNS)") (class "Default")
      (node (ref "C59") (pin "1") (pinfunction "1_1") (pintype "passive"))
      (node (ref "LDO_2") (pin "3") (pinfunction "FB/SNS_3") (pintype "bidirectional"))
      (node (ref "R6") (pin "2") (pinfunction "2_2") (pintype "passive"))
      (node (ref "R7") (pin "1") (pinfunction "1_1") (pintype "passive"))
    )
    (net (code "57") (name "Net-(LDO_2-NR)") (class "Default")
      (node (ref "C58") (pin "1") (pinfunction "1_1") (pintype "passive"))
      (node (ref "LDO_2") (pin "6") (pinfunction "NR_6") (pintype "bidirectional"))
    )
    (net (code "58") (name "Net-(LDO_3-FB{slash}SNS)") (class "Default")
      (node (ref "C63") (pin "1") (pinfunction "1_1") (pintype "passive"))
      (node (ref "LDO_3") (pin "3") (pinfunction "FB/SNS_3") (pintype "bidirectional"))
      (node (ref "R10") (pin "1") (pinfunction "1_1") (pintype "passive"))
      (node (ref "R9") (pin "2") (pinfunction "2_2") (pintype "passive"))
    )
    (net (code "59") (name "Net-(LDO_3-NR)") (class "Default")
      (node (ref "C62") (pin "1") (pinfunction "1_1") (pintype "passive"))
      (node (ref "LDO_3") (pin "6") (pinfunction "NR_6") (pintype "bidirectional"))
    )
    (net (code "60") (name "Net-(LDO_4-FB{slash}SNS)") (class "Default")
      (node (ref "C67") (pin "1") (pinfunction "1_1") (pintype "passive"))
      (node (ref "LDO_4") (pin "3") (pinfunction "FB/SNS_3") (pintype "bidirectional"))
      (node (ref "R12") (pin "2") (pinfunction "2_2") (pintype "passive"))
      (node (ref "R14") (pin "1") (pinfunction "1_1") (pintype "passive"))
    )
    (net (code "61") (name "Net-(LDO_4-NR)") (class "Default")
      (node (ref "C66") (pin "1") (pinfunction "1_1") (pintype "passive"))
      (node (ref "LDO_4") (pin "6") (pinfunction "NR_6") (pintype "bidirectional"))
    )
    (net (code "62") (name "Net-(LDO_5-FB{slash}SNS)") (class "Default")
      (node (ref "C71") (pin "1") (pinfunction "1_1") (pintype "passive"))
      (node (ref "LDO_5") (pin "3") (pinfunction "FB/SNS_3") (pintype "bidirectional"))
      (node (ref "R16") (pin "2") (pinfunction "2_2") (pintype "passive"))
      (node (ref "R19") (pin "1") (pinfunction "1_1") (pintype "passive"))
    )
    (net (code "63") (name "Net-(LDO_5-NR)") (class "Default")
      (node (ref "C70") (pin "1") (pinfunction "1_1") (pintype "passive"))
      (node (ref "LDO_5") (pin "6") (pinfunction "NR_6") (pintype "bidirectional"))
    )
    (net (code "64") (name "Net-(LDO_6-FB{slash}SNS)") (class "Default")
      (node (ref "C77") (pin "1") (pinfunction "1_1") (pintype "passive"))
      (node (ref "LDO_6") (pin "3") (pinfunction "FB/SNS_3") (pintype "bidirectional"))
      (node (ref "R22") (pin "2") (pinfunction "2_2") (pintype "passive"))
      (node (ref "R23") (pin "1") (pinfunction "1_1") (pintype "passive"))
    )
    (net (code "65") (name "Net-(LDO_6-NR)") (class "Default")
      (node (ref "C76") (pin "1") (pinfunction "1_1") (pintype "passive"))
      (node (ref "LDO_6") (pin "6") (pinfunction "NR_6") (pintype "bidirectional"))
    )
    (net (code "66") (name "Net-(LDO_7-FB{slash}SNS)") (class "Default")
      (node (ref "C81") (pin "1") (pinfunction "1_1") (pintype "passive"))
      (node (ref "LDO_7") (pin "3") (pinfunction "FB/SNS_3") (pintype "bidirectional"))
      (node (ref "R25") (pin "2") (pinfunction "2_2") (pintype "passive"))
      (node (ref "R26") (pin "1") (pinfunction "1_1") (pintype "passive"))
    )
    (net (code "67") (name "Net-(LDO_7-NR)") (class "Default")
      (node (ref "C80") (pin "1") (pinfunction "1_1") (pintype "passive"))
      (node (ref "LDO_7") (pin "6") (pinfunction "NR_6") (pintype "bidirectional"))
    )
    (net (code "68") (name "Net-(LDO_8-FB{slash}SNS)") (class "Default")
      (node (ref "C85") (pin "1") (pinfunction "1_1") (pintype "passive"))
      (node (ref "LDO_8") (pin "3") (pinfunction "FB/SNS_3") (pintype "bidirectional"))
      (node (ref "R28") (pin "2") (pinfunction "2_2") (pintype "passive"))
      (node (ref "R29") (pin "1") (pinfunction "1_1") (pintype "passive"))
    )
    (net (code "69") (name "Net-(LDO_8-NR)") (class "Default")
      (node (ref "C84") (pin "1") (pinfunction "1_1") (pintype "passive"))
      (node (ref "LDO_8") (pin "6") (pinfunction "NR_6") (pintype "bidirectional"))
    )
    (net (code "70") (name "Net-(LDO_9-FB{slash}SNS)") (class "Default")
      (node (ref "C89") (pin "1") (pinfunction "1_1") (pintype "passive"))
      (node (ref "LDO_9") (pin "3") (pinfunction "FB/SNS_3") (pintype "bidirectional"))
      (node (ref "R31") (pin "2") (pinfunction "2_2") (pintype "passive"))
      (node (ref "R32") (pin "1") (pinfunction "1_1") (pintype "passive"))
    )
    (net (code "71") (name "Net-(LDO_9-NR)") (class "Default")
      (node (ref "C88") (pin "1") (pinfunction "1_1") (pintype "passive"))
      (node (ref "LDO_9") (pin "6") (pinfunction "NR_6") (pintype "bidirectional"))
    )
    (net (code "72") (name "Net-(LDO_10-FB{slash}SNS)") (class "Default")
      (node (ref "C93") (pin "1") (pinfunction "1_1") (pintype "passive"))
      (node (ref "LDO_10") (pin "3") (pinfunction "FB/SNS_3") (pintype "bidirectional"))
      (node (ref "R34") (pin "2") (pinfunction "2_2") (pintype "passive"))
      (node (ref "R35") (pin "1") (pinfunction "1_1") (pintype "passive"))
    )
    (net (code "73") (name "Net-(LDO_10-NR)") (class "Default")
      (node (ref "C92") (pin "1") (pinfunction "1_1") (pintype "passive"))
      (node (ref "LDO_10") (pin "6") (pinfunction "NR_6") (pintype "bidirectional"))
    )
    (net (code "74") (name "Net-(LDO_11-FB{slash}SNS)") (class "Default")
      (node (ref "C97") (pin "1") (pinfunction "1_1") (pintype "passive"))
      (node (ref "LDO_11") (pin "3") (pinfunction "FB/SNS_3") (pintype "bidirectional"))
      (node (ref "R37") (pin "2") (pinfunction "2_2") (pintype "passive"))
      (node (ref "R38") (pin "1") (pinfunction "1_1") (pintype "passive"))
    )
    (net (code "75") (name "Net-(LDO_11-NR)") (class "Default")
      (node (ref "C96") (pin "1") (pinfunction "1_1") (pintype "passive"))
      (node (ref "LDO_11") (pin "6") (pinfunction "NR_6") (pintype "bidirectional"))
    )
    (net (code "76") (name "Net-(LDO_12-EN)") (class "Default")
      (node (ref "LDO_12") (pin "5") (pinfunction "EN_5") (pintype "bidirectional"))
      (node (ref "R39") (pin "2") (pinfunction "2_2") (pintype "passive"))
    )
    (net (code "77") (name "Net-(LDO_12-FB{slash}SNS)") (class "Default")
      (node (ref "C101") (pin "1") (pinfunction "1_1") (pintype "passive"))
      (node (ref "LDO_12") (pin "3") (pinfunction "FB/SNS_3") (pintype "bidirectional"))
      (node (ref "R40") (pin "2") (pinfunction "2_2") (pintype "passive"))
      (node (ref "R41") (pin "1") (pinfunction "1_1") (pintype "passive"))
    )
    (net (code "78") (name "Net-(LDO_12-NR)") (class "Default")
      (node (ref "C100") (pin "1") (pinfunction "1_1") (pintype "passive"))
      (node (ref "LDO_12") (pin "6") (pinfunction "NR_6") (pintype "bidirectional"))
    )
    (net (code "79") (name "Net-(LED1-PadA)") (class "Default")
      (node (ref "LED1") (pin "A") (pinfunction "A_A") (pintype "passive"))
      (node (ref "R201") (pin "1") (pinfunction "1_1") (pintype "passive"))
    )
    (net (code "80") (name "Net-(LNA_1-RF_IN)") (class "Default")
      (node (ref "C1") (pin "2") (pinfunction "2_2") (pintype "passive"))
      (node (ref "LNA_1") (pin "3") (pinfunction "RF_IN_3") (pintype "bidirectional"))
    )
    (net (code "81") (name "Net-(LNA_1-RF_OUT)") (class "Default")
      (node (ref "C4") (pin "1") (pinfunction "1_1") (pintype "passive"))
      (node (ref "L1") (pin "1") (pinfunction "1_1") (pintype "passive"))
      (node (ref "LNA_1") (pin "1") (pinfunction "RF_OUT_1") (pintype "bidirectional"))
    )
    (net (code "82") (name "Net-(LNA_2-RF_IN)") (class "Default")
      (node (ref "C5") (pin "2") (pinfunction "2_2") (pintype "passive"))
      (node (ref "LNA_2") (pin "3") (pinfunction "RF_IN_3") (pintype "bidirectional"))
    )
    (net (code "83") (name "Net-(LNA_2-RF_OUT)") (class "Default")
      (node (ref "C8") (pin "2") (pinfunction "2_2") (pintype "passive"))
      (node (ref "L4") (pin "1") (pinfunction "1_1") (pintype "passive"))
      (node (ref "LNA_2") (pin "1") (pinfunction "RF_OUT_1") (pintype "bidirectional"))
    )
    (net (code "84") (name "Net-(LNA_3-RF_IN)") (class "Default")
      (node (ref "C9") (pin "2") (pinfunction "2_2") (pintype "passive"))
      (node (ref "LNA_3") (pin "3") (pinfunction "RF_IN_3") (pintype "bidirectional"))
    )
    (net (code "85") (name "Net-(LNA_3-RF_OUT)") (class "Default")
      (node (ref "C12") (pin "1") (pinfunction "1_1") (pintype "passive"))
      (node (ref "L7") (pin "2") (pinfunction "2_2") (pintype "passive"))
      (node (ref "LNA_3") (pin "1") (pinfunction "RF_OUT_1") (pintype "bidirectional"))
    )
    (net (code "86") (name "Net-(LNA_4-RF_IN)") (class "Default")
      (node (ref "C14") (pin "2") (pinfunction "2_2") (pintype "passive"))
      (node (ref "LNA_4") (pin "3") (pinfunction "RF_IN_3") (pintype "bidirectional"))
    )
    (net (code "87") (name "Net-(LNA_4-RF_OUT)") (class "Default")
      (node (ref "C17") (pin "1") (pinfunction "1_1") (pintype "passive"))
      (node (ref "L10") (pin "1") (pinfunction "1_1") (pintype "passive"))
      (node (ref "LNA_4") (pin "1") (pinfunction "RF_OUT_1") (pintype "bidirectional"))
    )
    (net (code "88") (name "Net-(LNA_5-RF_IN)") (class "Default")
      (node (ref "C18") (pin "2") (pinfunction "2_2") (pintype "passive"))
      (node (ref "LNA_5") (pin "3") (pinfunction "RF_IN_3") (pintype "bidirectional"))
    )
    (net (code "89") (name "Net-(LNA_5-RF_OUT)") (class "Default")
      (node (ref "C21") (pin "1") (pinfunction "1_1") (pintype "passive"))
      (node (ref "L11") (pin "1") (pinfunction "1_1") (pintype "passive"))
      (node (ref "LNA_5") (pin "1") (pinfunction "RF_OUT_1") (pintype "bidirectional"))
    )
    (net (code "90") (name "Net-(LNA_6-RF_IN)") (class "Default")
      (node (ref "C22") (pin "2") (pinfunction "2_2") (pintype "passive"))
      (node (ref "LNA_6") (pin "3") (pinfunction "RF_IN_3") (pintype "bidirectional"))
    )
    (net (code "91") (name "Net-(LNA_6-RF_OUT)") (class "Default")
      (node (ref "C25") (pin "1") (pinfunction "1_1") (pintype "passive"))
      (node (ref "L12") (pin "2") (pinfunction "2_2") (pintype "passive"))
      (node (ref "LNA_6") (pin "1") (pinfunction "RF_OUT_1") (pintype "bidirectional"))
    )
    (net (code "92") (name "Net-(LNA_7-RF_IN)") (class "Default")
      (node (ref "C26") (pin "2") (pinfunction "2_2") (pintype "passive"))
      (node (ref "LNA_7") (pin "3") (pinfunction "RF_IN_3") (pintype "bidirectional"))
    )
    (net (code "93") (name "Net-(LNA_7-RF_OUT)") (class "Default")
      (node (ref "C29") (pin "1") (pinfunction "1_1") (pintype "passive"))
      (node (ref "L13") (pin "1") (pinfunction "1_1") (pintype "passive"))
      (node (ref "LNA_7") (pin "1") (pinfunction "RF_OUT_1") (pintype "bidirectional"))
    )
    (net (code "94") (name "Net-(LNA_8-RF_IN)") (class "Default")
      (node (ref "C30") (pin "2") (pinfunction "2_2") (pintype "passive"))
      (node (ref "LNA_8") (pin "3") (pinfunction "RF_IN_3") (pintype "bidirectional"))
    )
    (net (code "95") (name "Net-(LNA_8-RF_OUT)") (class "Default")
      (node (ref "C33") (pin "1") (pinfunction "1_1") (pintype "passive"))
      (node (ref "L14") (pin "1") (pinfunction "1_1") (pintype "passive"))
      (node (ref "LNA_8") (pin "1") (pinfunction "RF_OUT_1") (pintype "bidirectional"))
    )
    (net (code "96") (name "Net-(LNA_9-RF_IN)") (class "Default")
      (node (ref "C34") (pin "2") (pinfunction "2_2") (pintype "passive"))
      (node (ref "LNA_9") (pin "3") (pinfunction "RF_IN_3") (pintype "bidirectional"))
    )
    (net (code "97") (name "Net-(LNA_9-RF_OUT)") (class "Default")
      (node (ref "C37") (pin "1") (pinfunction "1_1") (pintype "passive"))
      (node (ref "L15") (pin "1") (pinfunction "1_1") (pintype "passive"))
      (node (ref "LNA_9") (pin "1") (pinfunction "RF_OUT_1") (pintype "bidirectional"))
    )
    (net (code "98") (name "Net-(LNA_10-RF_IN)") (class "Default")
      (node (ref "C39") (pin "2") (pinfunction "2_2") (pintype "passive"))
      (node (ref "L17") (pin "1") (pinfunction "1_1") (pintype "passive"))
      (node (ref "LNA_10") (pin "3") (pinfunction "RF_IN_3") (pintype "bidirectional"))
    )
    (net (code "99") (name "Net-(LNA_10-RF_OUT)") (class "Default")
      (node (ref "C42") (pin "1") (pinfunction "1_1") (pintype "passive"))
      (node (ref "L18") (pin "1") (pinfunction "1_1") (pintype "passive"))
      (node (ref "L19") (pin "1") (pinfunction "1_1") (pintype "passive"))
      (node (ref "LNA_10") (pin "1") (pinfunction "RF_OUT_1") (pintype "bidirectional"))
    )
    (net (code "100") (name "Net-(LNA_11-RF_IN)") (class "Default")
      (node (ref "C43") (pin "2") (pinfunction "2_2") (pintype "passive"))
      (node (ref "L20") (pin "1") (pinfunction "1_1") (pintype "passive"))
      (node (ref "LNA_11") (pin "3") (pinfunction "RF_IN_3") (pintype "bidirectional"))
    )
    (net (code "101") (name "Net-(LNA_11-RF_OUT)") (class "Default")
      (node (ref "C46") (pin "1") (pinfunction "1_1") (pintype "passive"))
      (node (ref "L21") (pin "1") (pinfunction "1_1") (pintype "passive"))
      (node (ref "L22") (pin "1") (pinfunction "1_1") (pintype "passive"))
      (node (ref "LNA_11") (pin "1") (pinfunction "RF_OUT_1") (pintype "bidirectional"))
    )
    (net (code "102") (name "Net-(LNA_12-RF_IN)") (class "Default")
      (node (ref "C47") (pin "2") (pinfunction "2_2") (pintype "passive"))
      (node (ref "L23") (pin "1") (pinfunction "1_1") (pintype "passive"))
      (node (ref "LNA_12") (pin "3") (pinfunction "RF_IN_3") (pintype "bidirectional"))
    )
    (net (code "103") (name "Net-(LNA_12-RF_OUT)") (class "Default")
      (node (ref "C50") (pin "1") (pinfunction "1_1") (pintype "passive"))
      (node (ref "L24") (pin "1") (pinfunction "1_1") (pintype "passive"))
      (node (ref "L25") (pin "1") (pinfunction "1_1") (pintype "passive"))
      (node (ref "LNA_12") (pin "1") (pinfunction "RF_OUT_1") (pintype "bidirectional"))
    )
    (net (code "104") (name "Net-(SAW_1-INPUT)") (class "Default")
      (node (ref "SAW_1") (pin "1") (pinfunction "INPUT_1") (pintype "bidirectional"))
      (node (ref "X1") (pin "1") (pinfunction "1_1") (pintype "passive"))
    )
    (net (code "105") (name "Net-(SAW_1-OUTPUT)") (class "Default")
      (node (ref "C1") (pin "1") (pinfunction "1_1") (pintype "passive"))
      (node (ref "SAW_1") (pin "8") (pinfunction "OUTPUT_8") (pintype "bidirectional"))
      (node (ref "X2") (pin "1") (pinfunction "1_1") (pintype "passive"))
    )
    (net (code "106") (name "Net-(SAW_2-INPUT)") (class "Default")
      (node (ref "C4") (pin "2") (pinfunction "2_2") (pintype "passive"))
      (node (ref "L2") (pin "2") (pinfunction "2_2") (pintype "passive"))
      (node (ref "SAW_2") (pin "2") (pinfunction "INPUT_2") (pintype "bidirectional"))
      (node (ref "X3") (pin "1") (pinfunction "1_1") (pintype "passive"))
    )
    (net (code "107") (name "Net-(SAW_2-OUTPUT)") (class "Default")
      (node (ref "C5") (pin "1") (pinfunction "1_1") (pintype "passive"))
      (node (ref "L3") (pin "2") (pinfunction "2_2") (pintype "passive"))
      (node (ref "SAW_2") (pin "6") (pinfunction "OUTPUT_6") (pintype "bidirectional"))
      (node (ref "X4") (pin "1") (pinfunction "1_1") (pintype "passive"))
    )
    (net (code "108") (name "Net-(SAW_3-INPUT)") (class "Default")
      (node (ref "C8") (pin "1") (pinfunction "1_1") (pintype "passive"))
      (node (ref "L5") (pin "2") (pinfunction "2_2") (pintype "passive"))
      (node (ref "SAW_3") (pin "2") (pinfunction "INPUT_2") (pintype "bidirectional"))
      (node (ref "X5") (pin "1") (pinfunction "1_1") (pintype "passive"))
    )
    (net (code "109") (name "Net-(SAW_3-OUTPUT)") (class "Default")
      (node (ref "C9") (pin "1") (pinfunction "1_1") (pintype "passive"))
      (node (ref "L6") (pin "2") (pinfunction "2_2") (pintype "passive"))
      (node (ref "SAW_3") (pin "6") (pinfunction "OUTPUT_6") (pintype "bidirectional"))
      (node (ref "X6") (pin "1") (pinfunction "1_1") (pintype "passive"))
    )
    (net (code "110") (name "Net-(SAW_4-INPUT)") (class "Default")
      (node (ref "C12") (pin "2") (pinfunction "2_2") (pintype "passive"))
      (node (ref "L8") (pin "2") (pinfunction "2_2") (pintype "passive"))
      (node (ref "SAW_4") (pin "2") (pinfunction "INPUT_2") (pintype "bidirectional"))
      (node (ref "X7") (pin "1") (pinfunction "1_1") (pintype "passive"))
    )
    (net (code "111") (name "Net-(SAW_4-OUTPUT)") (class "Default")
      (node (ref "C13") (pin "1") (pinfunction "1_1") (pintype "passive"))
      (node (ref "L9") (pin "2") (pinfunction "2_2") (pintype "passive"))
      (node (ref "SAW_4") (pin "6") (pinfunction "OUTPUT_6") (pintype "bidirectional"))
    )
    (net (code "112") (name "Net-(SAW_5-INPUT)") (class "Default")
      (node (ref "C17") (pin "2") (pinfunction "2_2") (pintype "passive"))
      (node (ref "SAW_5") (pin "2") (pinfunction "INPUT_2") (pintype "bidirectional"))
      (node (ref "X10") (pin "1") (pinfunction "1_1") (pintype "passive"))
    )
    (net (code "113") (name "Net-(SAW_5-OUTPUT)") (class "Default")
      (node (ref "C18") (pin "1") (pinfunction "1_1") (pintype "passive"))
      (node (ref "SAW_5") (pin "6") (pinfunction "OUTPUT_6") (pintype "bidirectional"))
      (node (ref "X11") (pin "1") (pinfunction "1_1") (pintype "passive"))
    )
    (net (code "114") (name "Net-(SAW_6-INPUT)") (class "Default")
      (node (ref "C21") (pin "2") (pinfunction "2_2") (pintype "passive"))
      (node (ref "SAW_6") (pin "2") (pinfunction "INPUT_2") (pintype "bidirectional"))
      (node (ref "X12") (pin "1") (pinfunction "1_1") (pintype "passive"))
    )
    (net (code "115") (name "Net-(SAW_6-OUTPUT)") (class "Default")
      (node (ref "C22") (pin "1") (pinfunction "1_1") (pintype "passive"))
      (node (ref "SAW_6") (pin "6") (pinfunction "OUTPUT_6") (pintype "bidirectional"))
      (node (ref "X13") (pin "1") (pinfunction "1_1") (pintype "passive"))
    )
    (net (code "116") (name "Net-(SAW_7-INPUT)") (class "Default")
      (node (ref "C25") (pin "2") (pinfunction "2_2") (pintype "passive"))
      (node (ref "SAW_7") (pin "2") (pinfunction "INPUT_2") (pintype "bidirectional"))
      (node (ref "X14") (pin "1") (pinfunction "1_1") (pintype "passive"))
    )
    (net (code "117") (name "Net-(SAW_7-OUTPUT)") (class "Default")
      (node (ref "SAW_7") (pin "6") (pinfunction "OUTPUT_6") (pintype "bidirectional"))
      (node (ref "SAW_8") (pin "2") (pinfunction "INPUT_2") (pintype "bidirectional"))
      (node (ref "X15") (pin "1") (pinfunction "1_1") (pintype "passive"))
    )
    (net (code "118") (name "Net-(SAW_8-OUTPUT)") (class "Default")
      (node (ref "SAW_8") (pin "6") (pinfunction "OUTPUT_6") (pintype "bidirectional"))
      (node (ref "X16") (pin "1") (pinfunction "1_1") (pintype "passive"))
    )
    (net (code "119") (name "Net-(SAW_9-INPUT)") (class "Default")
      (node (ref "C29") (pin "2") (pinfunction "2_2") (pintype "passive"))
      (node (ref "SAW_9") (pin "2") (pinfunction "INPUT_2") (pintype "bidirectional"))
      (node (ref "X18") (pin "1") (pinfunction "1_1") (pintype "passive"))
    )
    (net (code "120") (name "Net-(SAW_9-OUTPUT)") (class "Default")
      (node (ref "C30") (pin "1") (pinfunction "1_1") (pintype "passive"))
      (node (ref "SAW_9") (pin "5") (pinfunction "OUTPUT_5") (pintype "bidirectional"))
      (node (ref "X19") (pin "1") (pinfunction "1_1") (pintype "passive"))
    )
    (net (code "121") (name "Net-(SAW_10-INPUT)") (class "Default")
      (node (ref "C33") (pin "2") (pinfunction "2_2") (pintype "passive"))
      (node (ref "SAW_10") (pin "2") (pinfunction "INPUT_2") (pintype "bidirectional"))
      (node (ref "X20") (pin "1") (pinfunction "1_1") (pintype "passive"))
    )
    (net (code "122") (name "Net-(SAW_10-OUTPUT)") (class "Default")
      (node (ref "C34") (pin "1") (pinfunction "1_1") (pintype "passive"))
      (node (ref "SAW_10") (pin "5") (pinfunction "OUTPUT_5") (pintype "bidirectional"))
      (node (ref "X21") (pin "1") (pinfunction "1_1") (pintype "passive"))
    )
    (net (code "123") (name "Net-(SAW_11-INPUT)") (class "Default")
      (node (ref "C37") (pin "2") (pinfunction "2_2") (pintype "passive"))
      (node (ref "SAW_11") (pin "2") (pinfunction "INPUT_2") (pintype "bidirectional"))
      (node (ref "X22") (pin "1") (pinfunction "1_1") (pintype "passive"))
    )
    (net (code "124") (name "Net-(SAW_11-OUTPUT)") (class "Default")
      (node (ref "SAW_11") (pin "5") (pinfunction "OUTPUT_5") (pintype "bidirectional"))
      (node (ref "SAW_12") (pin "2") (pinfunction "INPUT_2") (pintype "bidirectional"))
      (node (ref "X23") (pin "1") (pinfunction "1_1") (pintype "passive"))
    )
    (net (code "125") (name "Net-(SAW_12-OUTPUT)") (class "Default")
      (node (ref "SAW_12") (pin "5") (pinfunction "OUTPUT_5") (pintype "bidirectional"))
      (node (ref "X24") (pin "1") (pinfunction "1_1") (pintype "passive"))
    )
    (net (code "126") (name "Net-(SAW_13-INPUT)") (class "Default")
      (node (ref "C38") (pin "2") (pinfunction "2_2") (pintype "passive"))
      (node (ref "SAW_13") (pin "10") (pinfunction "INPUT_10") (pintype "bidirectional"))
    )
    (net (code "127") (name "Net-(SAW_13-OUTPUT)") (class "Default")
      (node (ref "C39") (pin "1") (pinfunction "1_1") (pintype "passive"))
      (node (ref "SAW_13") (pin "5") (pinfunction "OUTPUT_5") (pintype "bidirectional"))
      (node (ref "X26") (pin "1") (pinfunction "1_1") (pintype "passive"))
    )
    (net (code "128") (name "Net-(SAW_14-INPUT)") (class "Default")
      (node (ref "C42") (pin "2") (pinfunction "2_2") (pintype "passive"))
      (node (ref "SAW_14") (pin "10") (pinfunction "INPUT_10") (pintype "bidirectional"))
      (node (ref "X27") (pin "1") (pinfunction "1_1") (pintype "passive"))
    )
    (net (code "129") (name "Net-(SAW_14-OUTPUT)") (class "Default")
      (node (ref "C43") (pin "1") (pinfunction "1_1") (pintype "passive"))
      (node (ref "SAW_14") (pin "5") (pinfunction "OUTPUT_5") (pintype "bidirectional"))
      (node (ref "X28") (pin "1") (pinfunction "1_1") (pintype "passive"))
    )
    (net (code "130") (name "Net-(SAW_15-INPUT)") (class "Default")
      (node (ref "C46") (pin "2") (pinfunction "2_2") (pintype "passive"))
      (node (ref "SAW_15") (pin "10") (pinfunction "INPUT_10") (pintype "bidirectional"))
      (node (ref "X29") (pin "1") (pinfunction "1_1") (pintype "passive"))
    )
    (net (code "131") (name "Net-(SAW_15-OUTPUT)") (class "Default")
      (node (ref "C47") (pin "1") (pinfunction "1_1") (pintype "passive"))
      (node (ref "SAW_15") (pin "5") (pinfunction "OUTPUT_5") (pintype "bidirectional"))
      (node (ref "X30") (pin "1") (pinfunction "1_1") (pintype "passive"))
    )
    (net (code "132") (name "Net-(SAW_16-INPUT)") (class "Default")
      (node (ref "C50") (pin "2") (pinfunction "2_2") (pintype "passive"))
      (node (ref "SAW_16") (pin "10") (pinfunction "INPUT_10") (pintype "bidirectional"))
      (node (ref "X31") (pin "1") (pinfunction "1_1") (pintype "passive"))
    )
    (net (code "133") (name "Net-(SAW_16-OUTPUT)") (class "Default")
      (node (ref "C51") (pin "1") (pinfunction "1_1") (pintype "passive"))
      (node (ref "SAW_16") (pin "5") (pinfunction "OUTPUT_5") (pintype "bidirectional"))
    )
    (net (code "134") (name "PRE_PWR_10") (class "Default")
      (node (ref "LDO_1") (pin "5") (pinfunction "EN_5") (pintype "bidirectional"))
      (node (ref "LDO_10") (pin "5") (pinfunction "EN_5") (pintype "bidirectional"))
      (node (ref "LDO_11") (pin "5") (pinfunction "EN_5") (pintype "bidirectional"))
      (node (ref "LDO_2") (pin "5") (pinfunction "EN_5") (pintype "bidirectional"))
      (node (ref "LDO_3") (pin "5") (pinfunction "EN_5") (pintype "bidirectional"))
      (node (ref "LDO_4") (pin "5") (pinfunction "EN_5") (pintype "bidirectional"))
      (node (ref "LDO_5") (pin "5") (pinfunction "EN_5") (pintype "bidirectional"))
      (node (ref "LDO_6") (pin "5") (pinfunction "EN_5") (pintype "bidirectional"))
      (node (ref "LDO_7") (pin "5") (pinfunction "EN_5") (pintype "bidirectional"))
      (node (ref "LDO_8") (pin "5") (pinfunction "EN_5") (pintype "bidirectional"))
      (node (ref "LDO_9") (pin "5") (pinfunction "EN_5") (pintype "bidirectional"))
      (node (ref "R1") (pin "2") (pinfunction "2_2") (pintype "passive"))
      (node (ref "R11") (pin "2") (pinfunction "2_2") (pintype "passive"))
      (node (ref "R15") (pin "2") (pinfunction "2_2") (pintype "passive"))
      (node (ref "R21") (pin "2") (pinfunction "2_2") (pintype "passive"))
      (node (ref "R24") (pin "2") (pinfunction "2_2") (pintype "passive"))
      (node (ref "R27") (pin "2") (pinfunction "2_2") (pintype "passive"))
      (node (ref "R30") (pin "2") (pinfunction "2_2") (pintype "passive"))
      (node (ref "R33") (pin "2") (pinfunction "2_2") (pintype "passive"))
      (node (ref "R36") (pin "2") (pinfunction "2_2") (pintype "passive"))
      (node (ref "R5") (pin "2") (pinfunction "2_2") (pintype "passive"))
      (node (ref "R8") (pin "2") (pinfunction "2_2") (pintype "passive"))
    )
    (net (code "135") (name "VDD") (class "Default")
      (node (ref "R4") (pin "2") (pinfunction "2_2") (pintype "passive"))
    )
    (net (code "136") (name "unconnected-(IC58-ILIM-Pad6)") (class "Default")
      (node (ref "IC58") (pin "6") (pinfunction "ILIM_6") (pintype "bidirectional"))
    )
    (net (code "137") (name "unconnected-(IC58-ISHARE-Pad25)") (class "Default")
      (node (ref "IC58") (pin "25") (pinfunction "ISHARE_25") (pintype "bidirectional"))
    )
    (net (code "138") (name "unconnected-(IC58-OCP_SEL-Pad4)") (class "Default")
      (node (ref "IC58") (pin "4") (pinfunction "OCP_SEL_4") (pintype "bidirectional"))
    )
    (net (code "139") (name "unconnected-(IC58-SS{slash}TR-Pad28)") (class "Default")
      (node (ref "IC58") (pin "28") (pinfunction "SS/TR_28") (pintype "bidirectional"))
    )
    (net (code "140") (name "unconnected-(IC58-SYNC_OUT-Pad7)") (class "Default")
      (node (ref "IC58") (pin "7") (pinfunction "SYNC_OUT_7") (pintype "bidirectional"))
    )
  )
)
